# stm32_v0_8.net
KiCad netlist of a schematic drawn in EAGLE
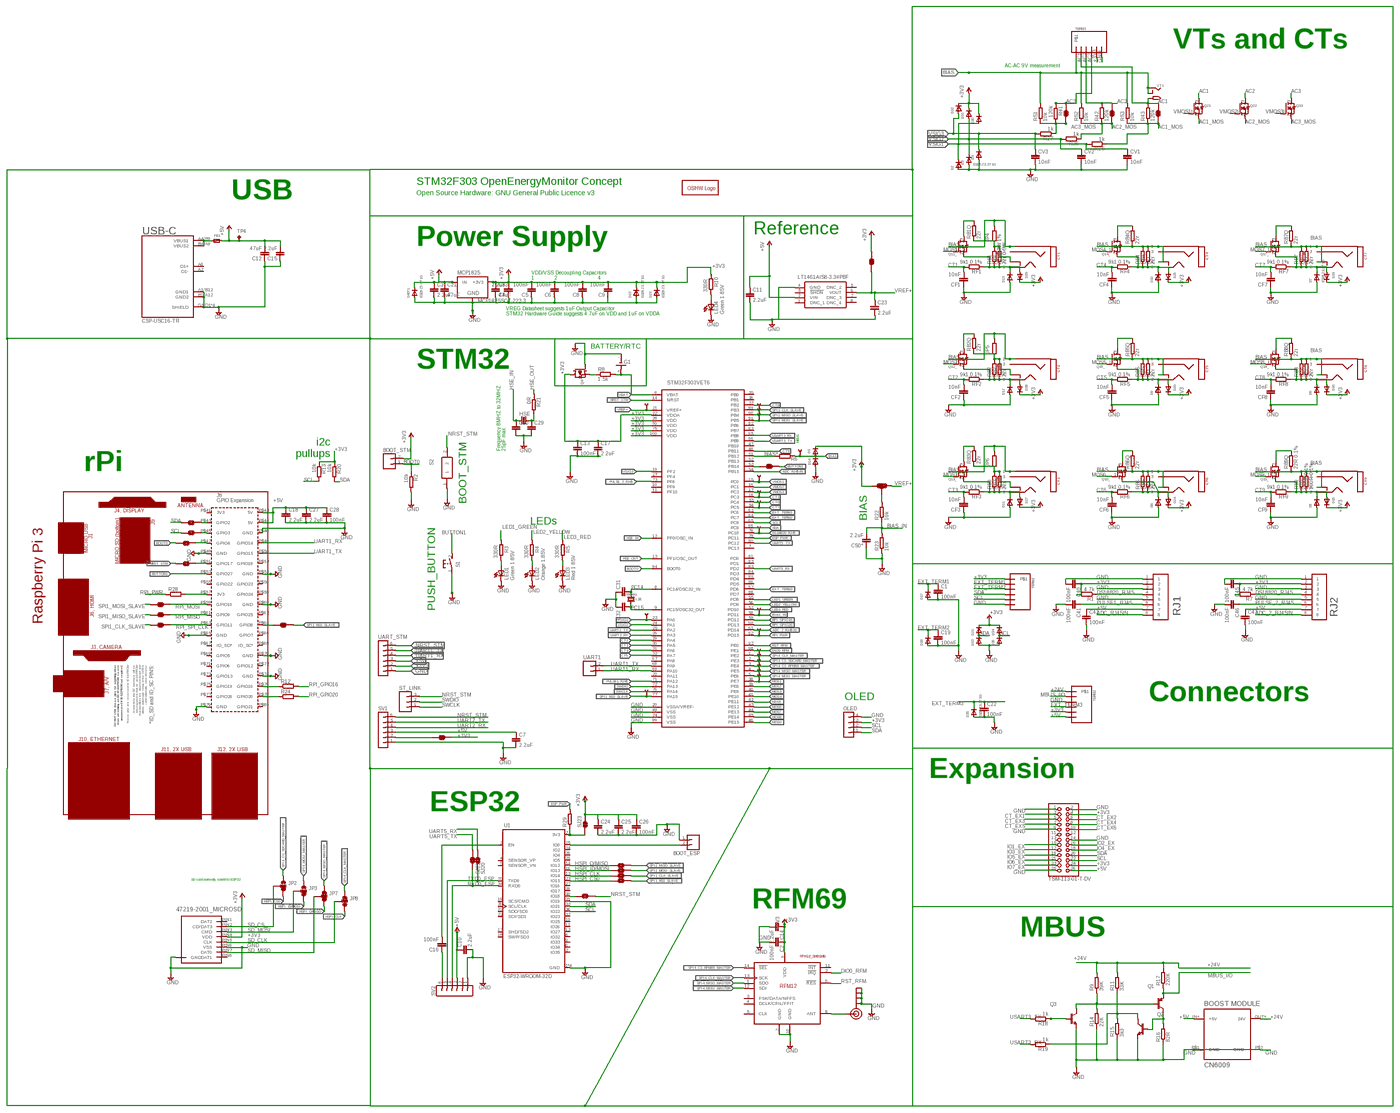
[diagram p0: schematic, sheet 1, overview]
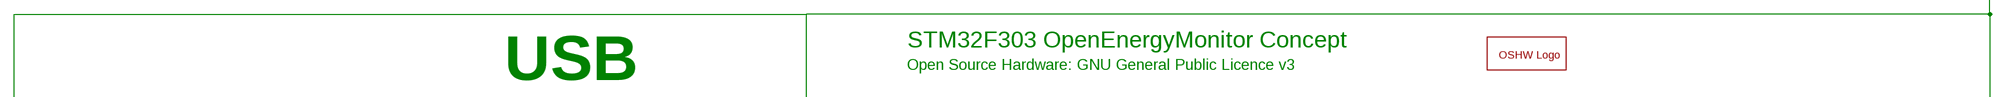
[diagram p1: schematic, sheet 1, part 1 of 4]
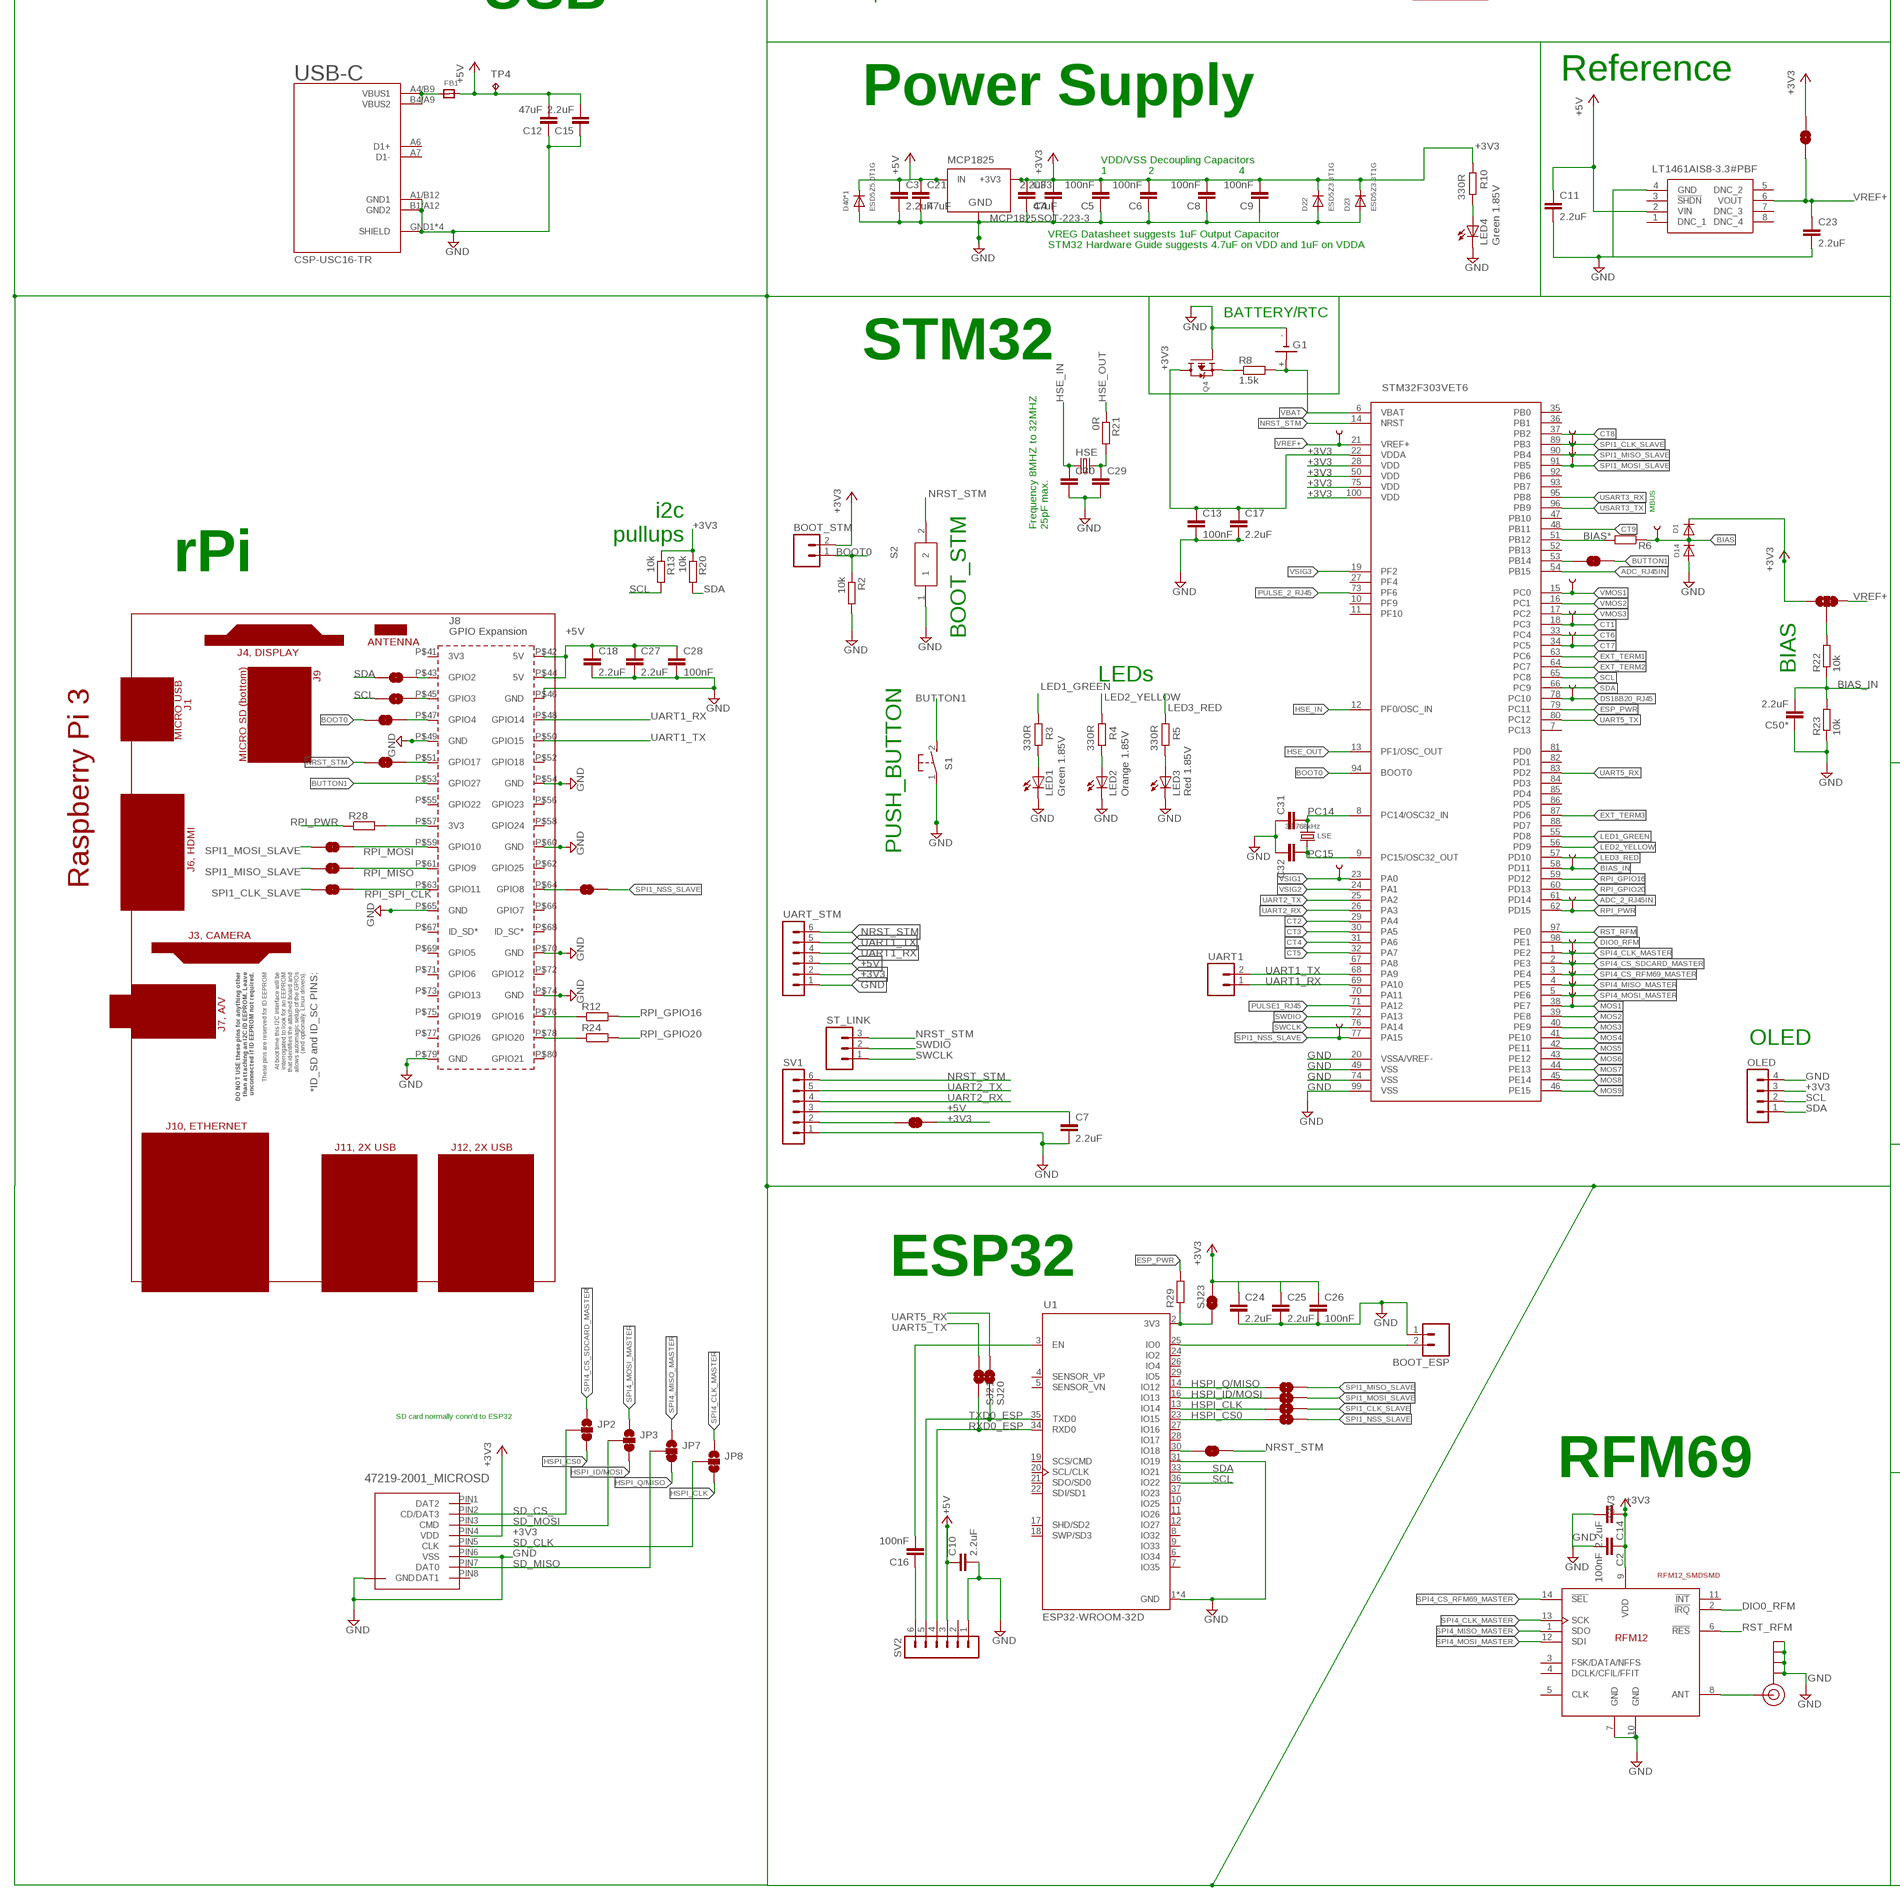
[diagram p2: schematic, sheet 1, part 2 of 4]
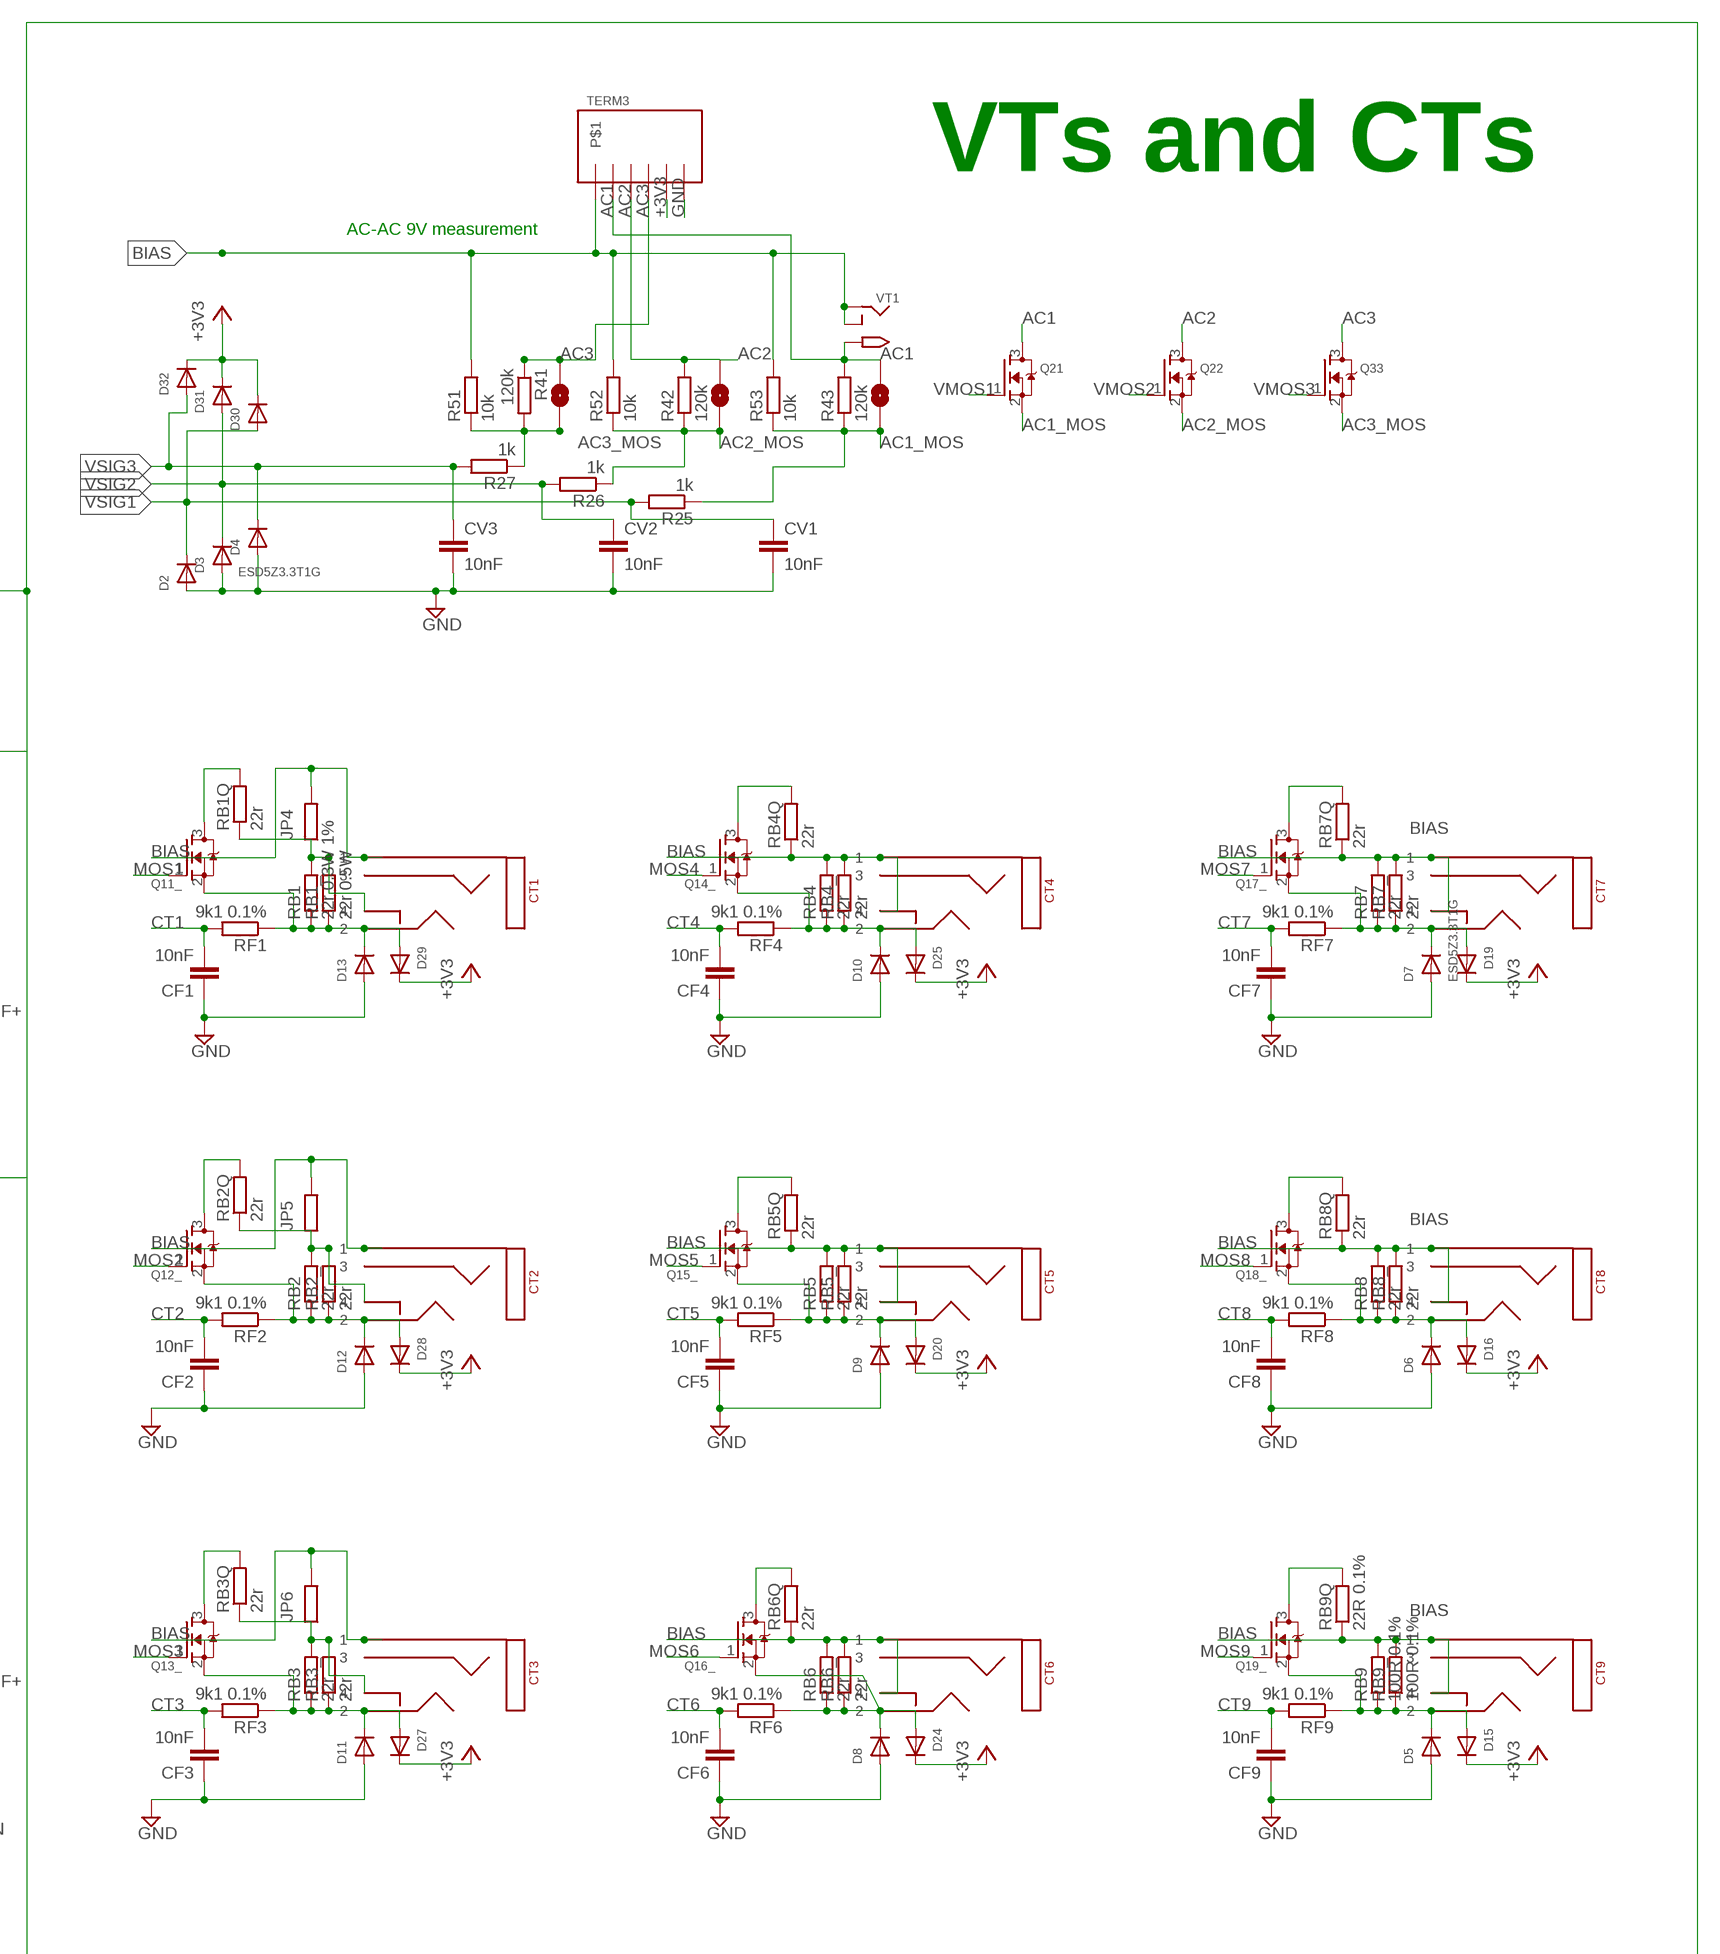
[diagram p3: schematic, sheet 1, part 3 of 4]
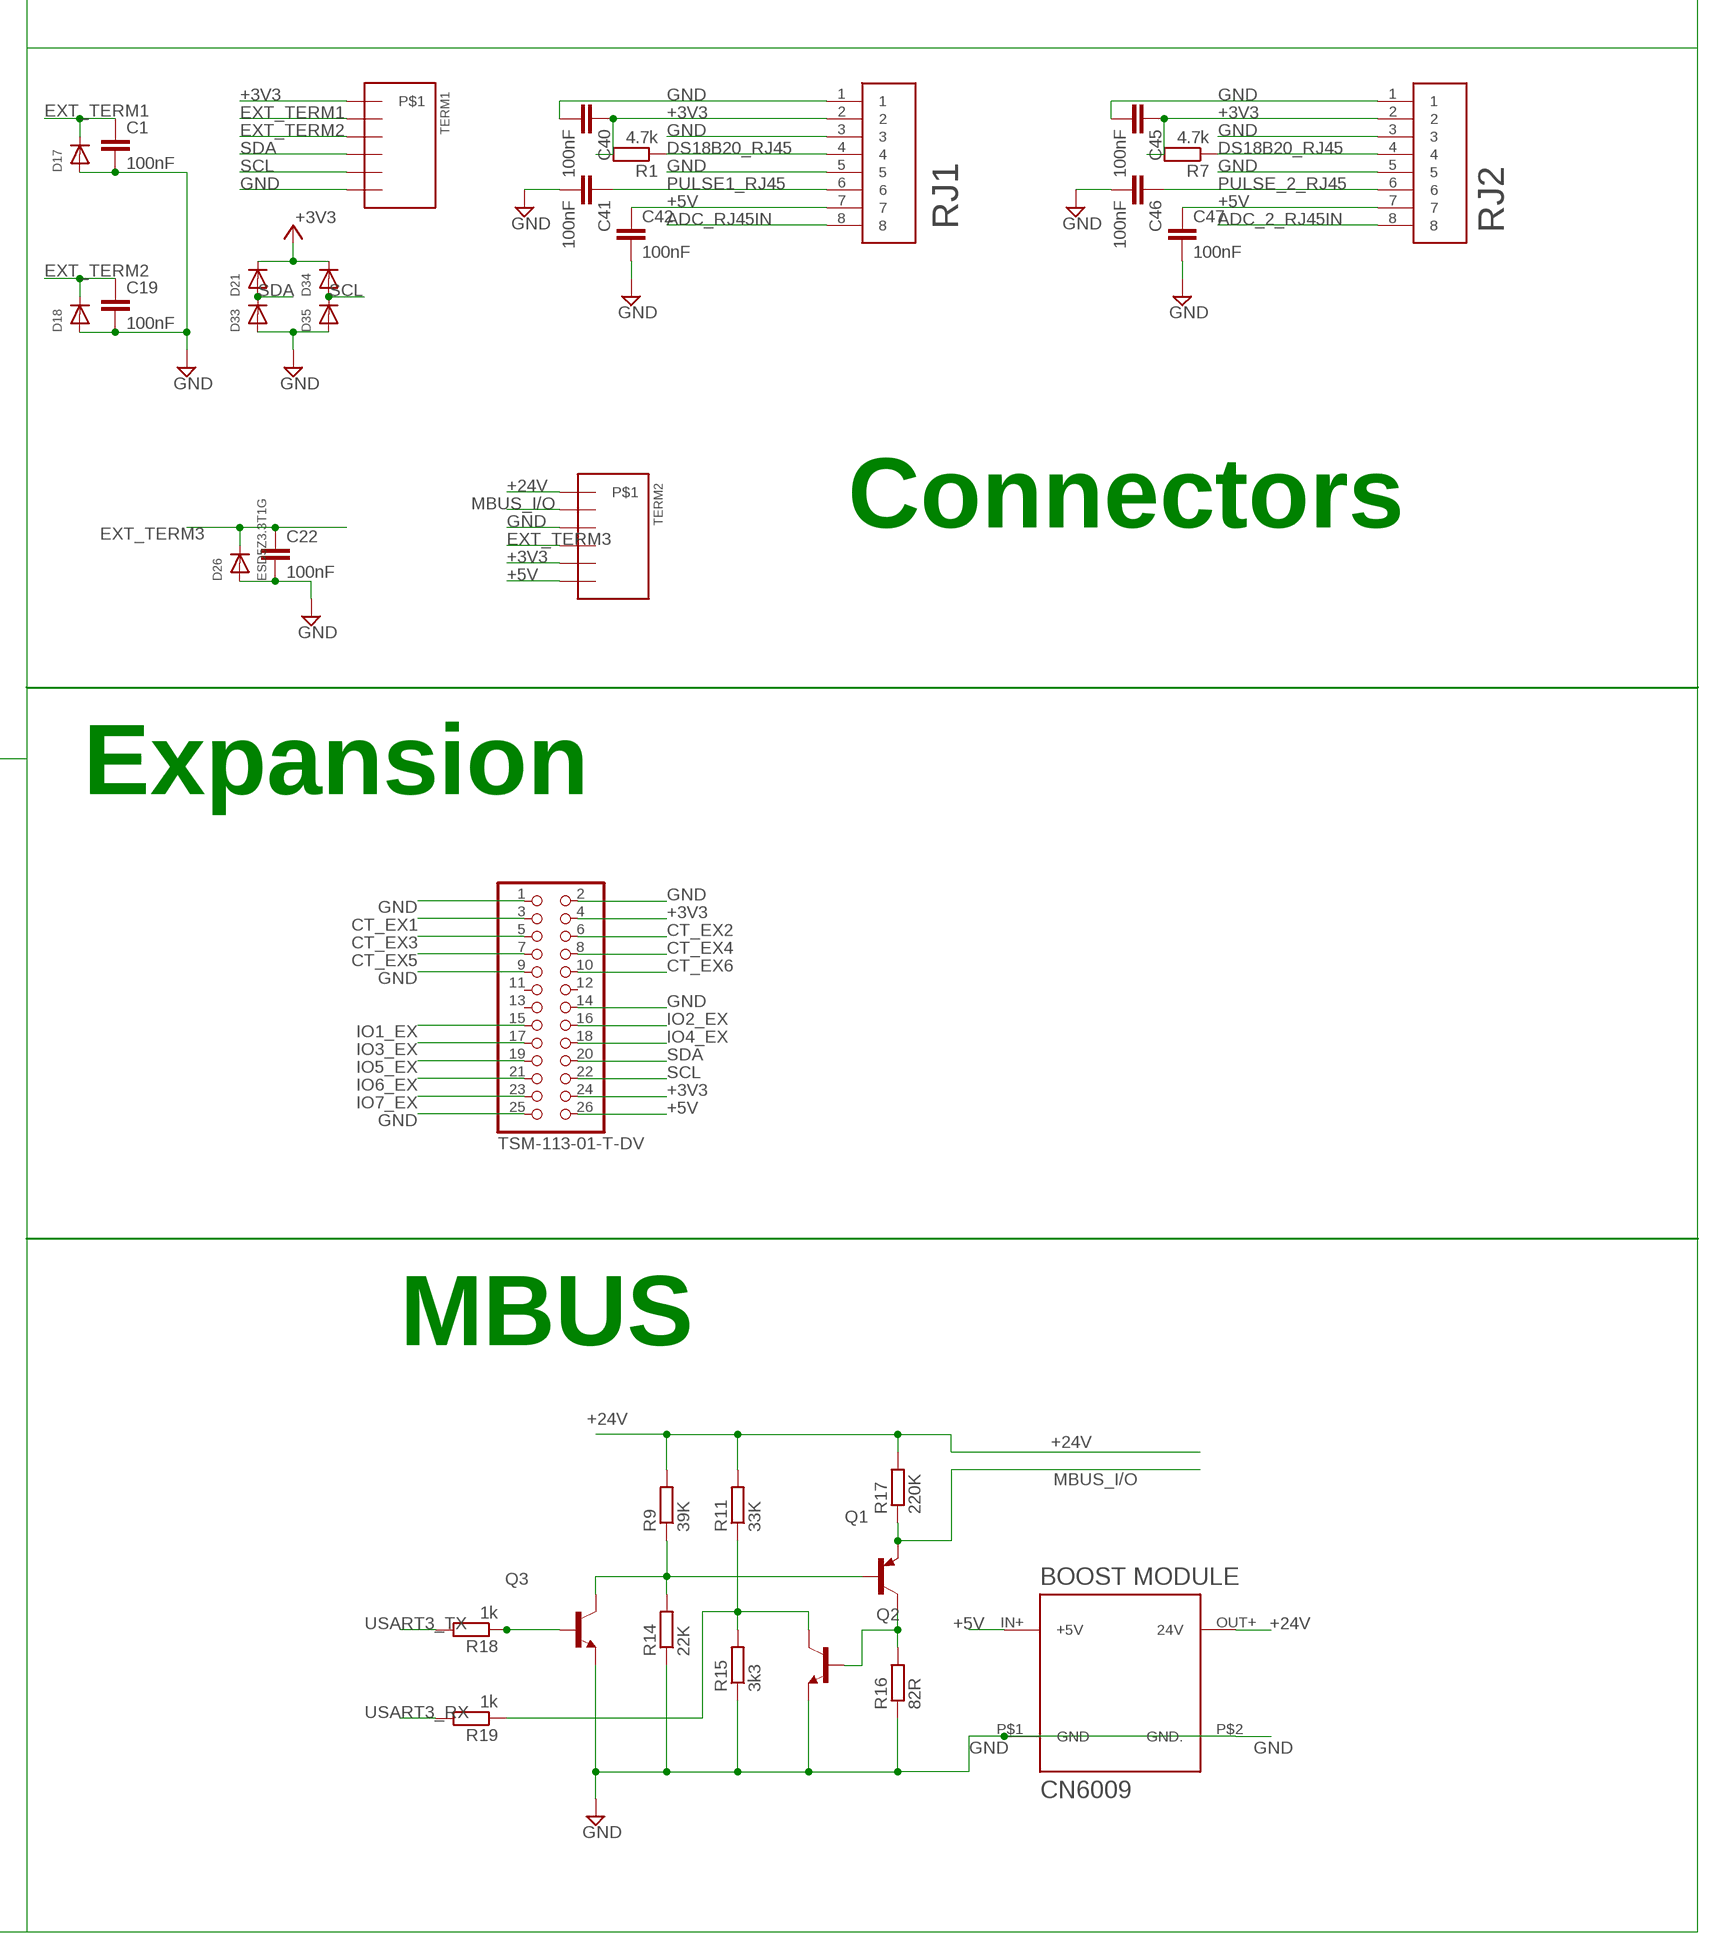
[diagram p4: schematic, sheet 1, part 4 of 4]

(export (version "E")
  (design (tool "Eeschema 10.0.6"))
  (components
    (comp (ref "BOOT_ESP")
      (value "M02PTH")
      (footprint "eagle-import:1X02")
      (libsource (lib "eagle-import") (part "M02PTH"))
    )
    (comp (ref "BOOT_STM")
      (value "M02PTH")
      (footprint "eagle-import:1X02")
      (libsource (lib "eagle-import") (part "M02PTH"))
    )
    (comp (ref "C1")
      (value "100nF")
      (footprint "eagle-import:C0603")
      (libsource (lib "eagle-import") (part "resistor_C-EUC0603"))
    )
    (comp (ref "C2")
      (value "100nF")
      (footprint "eagle-import:C0603")
      (libsource (lib "eagle-import") (part "resistor_C-EUC0603"))
    )
    (comp (ref "C3")
      (value "2.2uF")
      (footprint "eagle-import:C0805")
      (libsource (lib "eagle-import") (part "C-EUC0805"))
    )
    (comp (ref "C4")
      (value "2.2uF")
      (footprint "eagle-import:C0805")
      (libsource (lib "eagle-import") (part "C-EUC0805"))
    )
    (comp (ref "C5")
      (value "100nF")
      (footprint "eagle-import:C0603")
      (libsource (lib "eagle-import") (part "resistor_C-EUC0603"))
    )
    (comp (ref "C6")
      (value "100nF")
      (footprint "eagle-import:C0603")
      (libsource (lib "eagle-import") (part "resistor_C-EUC0603"))
    )
    (comp (ref "C7")
      (value "2.2uF")
      (footprint "eagle-import:C0805")
      (libsource (lib "eagle-import") (part "C-EUC0805"))
    )
    (comp (ref "C8")
      (value "100nF")
      (footprint "eagle-import:C0603")
      (libsource (lib "eagle-import") (part "resistor_C-EUC0603"))
    )
    (comp (ref "C9")
      (value "100nF")
      (footprint "eagle-import:C0603")
      (libsource (lib "eagle-import") (part "resistor_C-EUC0603"))
    )
    (comp (ref "C10")
      (value "2.2uF")
      (footprint "eagle-import:C0805")
      (libsource (lib "eagle-import") (part "C-EUC0805"))
    )
    (comp (ref "C11")
      (value "2.2uF")
      (footprint "eagle-import:C0805")
      (libsource (lib "eagle-import") (part "C-EUC0805"))
    )
    (comp (ref "C12")
      (value "47uF")
      (footprint "eagle-import:C0805")
      (libsource (lib "eagle-import") (part "C-EUC0805"))
    )
    (comp (ref "C13")
      (value "100nF")
      (footprint "eagle-import:C0603")
      (libsource (lib "eagle-import") (part "C-EUC0603"))
    )
    (comp (ref "C14")
      (value "2.2uF")
      (footprint "eagle-import:C0805")
      (libsource (lib "eagle-import") (part "C-EUC0805"))
    )
    (comp (ref "C15")
      (value "2.2uF")
      (footprint "eagle-import:C0805")
      (libsource (lib "eagle-import") (part "C-EUC0805"))
    )
    (comp (ref "C16")
      (value "100nF")
      (footprint "eagle-import:C0603")
      (libsource (lib "eagle-import") (part "resistor_C-EUC0603"))
    )
    (comp (ref "C17")
      (value "2.2uF")
      (footprint "eagle-import:C0805")
      (libsource (lib "eagle-import") (part "C-EUC0805"))
    )
    (comp (ref "C18")
      (value "2.2uF")
      (footprint "eagle-import:C0805")
      (libsource (lib "eagle-import") (part "C-EUC0805"))
    )
    (comp (ref "C19")
      (value "100nF")
      (footprint "eagle-import:C0603")
      (libsource (lib "eagle-import") (part "resistor_C-EUC0603"))
    )
    (comp (ref "C21")
      (value "47uF")
      (footprint "eagle-import:C0805")
      (libsource (lib "eagle-import") (part "C-EUC0805"))
    )
    (comp (ref "C22")
      (value "100nF")
      (footprint "eagle-import:C0603")
      (libsource (lib "eagle-import") (part "resistor_C-EUC0603"))
    )
    (comp (ref "C23")
      (value "2.2uF")
      (footprint "eagle-import:C0805")
      (libsource (lib "eagle-import") (part "C-EUC0805"))
    )
    (comp (ref "C24")
      (value "2.2uF")
      (footprint "eagle-import:C0805")
      (libsource (lib "eagle-import") (part "C-EUC0805"))
    )
    (comp (ref "C25")
      (value "2.2uF")
      (footprint "eagle-import:C0805")
      (libsource (lib "eagle-import") (part "C-EUC0805"))
    )
    (comp (ref "C26")
      (value "100nF")
      (footprint "eagle-import:C0603")
      (libsource (lib "eagle-import") (part "resistor_C-EUC0603"))
    )
    (comp (ref "C27")
      (value "2.2uF")
      (footprint "eagle-import:C0805")
      (libsource (lib "eagle-import") (part "C-EUC0805"))
    )
    (comp (ref "C28")
      (value "100nF")
      (footprint "eagle-import:C0603")
      (libsource (lib "eagle-import") (part "resistor_C-EUC0603"))
    )
    (comp (ref "C29")
      (value "15pF")
      (footprint "eagle-import:C0603")
      (libsource (lib "eagle-import") (part "C-EUC0603"))
    )
    (comp (ref "C30")
      (value "15pF")
      (footprint "eagle-import:C0603")
      (libsource (lib "eagle-import") (part "C-EUC0603"))
    )
    (comp (ref "C31")
      (value "10pF")
      (footprint "eagle-import:C0603")
      (libsource (lib "eagle-import") (part "C-EUC0603"))
    )
    (comp (ref "C32")
      (value "10pF")
      (footprint "eagle-import:C0603")
      (libsource (lib "eagle-import") (part "C-EUC0603"))
    )
    (comp (ref "C33")
      (value "47uF")
      (footprint "eagle-import:C0805")
      (libsource (lib "eagle-import") (part "C-EUC0805"))
    )
    (comp (ref "C40")
      (value "100nF")
      (footprint "eagle-import:C0603")
      (libsource (lib "eagle-import") (part "resistor_C-EUC0603"))
    )
    (comp (ref "C41")
      (value "100nF")
      (footprint "eagle-import:C0603")
      (libsource (lib "eagle-import") (part "resistor_C-EUC0603"))
    )
    (comp (ref "C42")
      (value "100nF")
      (footprint "eagle-import:C0603")
      (libsource (lib "eagle-import") (part "resistor_C-EUC0603"))
    )
    (comp (ref "C45")
      (value "100nF")
      (footprint "eagle-import:C0603")
      (libsource (lib "eagle-import") (part "resistor_C-EUC0603"))
    )
    (comp (ref "C46")
      (value "100nF")
      (footprint "eagle-import:C0603")
      (libsource (lib "eagle-import") (part "resistor_C-EUC0603"))
    )
    (comp (ref "C47")
      (value "100nF")
      (footprint "eagle-import:C0603")
      (libsource (lib "eagle-import") (part "resistor_C-EUC0603"))
    )
    (comp (ref "C50*")
      (value "2.2uF")
      (footprint "eagle-import:C0805")
      (libsource (lib "eagle-import") (part "C-EUC0805"))
    )
    (comp (ref "CF1")
      (value "10nF")
      (footprint "eagle-import:C0603")
      (libsource (lib "eagle-import") (part "resistor_C-EUC0603"))
    )
    (comp (ref "CF2")
      (value "10nF")
      (footprint "eagle-import:C0603")
      (libsource (lib "eagle-import") (part "resistor_C-EUC0603"))
    )
    (comp (ref "CF3")
      (value "10nF")
      (footprint "eagle-import:C0603")
      (libsource (lib "eagle-import") (part "resistor_C-EUC0603"))
    )
    (comp (ref "CF4")
      (value "10nF")
      (footprint "eagle-import:C0603")
      (libsource (lib "eagle-import") (part "resistor_C-EUC0603"))
    )
    (comp (ref "CF5")
      (value "10nF")
      (footprint "eagle-import:C0603")
      (libsource (lib "eagle-import") (part "resistor_C-EUC0603"))
    )
    (comp (ref "CF6")
      (value "10nF")
      (footprint "eagle-import:C0603")
      (libsource (lib "eagle-import") (part "resistor_C-EUC0603"))
    )
    (comp (ref "CF7")
      (value "10nF")
      (footprint "eagle-import:C0603")
      (libsource (lib "eagle-import") (part "resistor_C-EUC0603"))
    )
    (comp (ref "CF8")
      (value "10nF")
      (footprint "eagle-import:C0603")
      (libsource (lib "eagle-import") (part "resistor_C-EUC0603"))
    )
    (comp (ref "CF9")
      (value "10nF")
      (footprint "eagle-import:C0603")
      (libsource (lib "eagle-import") (part "resistor_C-EUC0603"))
    )
    (comp (ref "CT1")
      (value "SJ-3523-SMT")
      (footprint "eagle-import:STEREO_SMT")
      (libsource (lib "eagle-import") (part "STEREO_SMD"))
    )
    (comp (ref "CT2")
      (value "SJ-3523-SMT")
      (footprint "eagle-import:STEREO_SMT")
      (libsource (lib "eagle-import") (part "STEREO_SMD"))
    )
    (comp (ref "CT3")
      (value "SJ-3523-SMT")
      (footprint "eagle-import:STEREO_SMT")
      (libsource (lib "eagle-import") (part "STEREO_SMD"))
    )
    (comp (ref "CT4")
      (value "SJ-3523-SMT")
      (footprint "eagle-import:STEREO_SMT")
      (libsource (lib "eagle-import") (part "STEREO_SMD"))
    )
    (comp (ref "CT5")
      (value "SJ-3523-SMT")
      (footprint "eagle-import:STEREO_SMT")
      (libsource (lib "eagle-import") (part "STEREO_SMD"))
    )
    (comp (ref "CT6")
      (value "SJ-3523-SMT")
      (footprint "eagle-import:STEREO_SMT")
      (libsource (lib "eagle-import") (part "STEREO_SMD"))
    )
    (comp (ref "CT7")
      (value "SJ-3523-SMT")
      (footprint "eagle-import:STEREO_SMT")
      (libsource (lib "eagle-import") (part "STEREO_SMD"))
    )
    (comp (ref "CT8")
      (value "SJ-3523-SMT")
      (footprint "eagle-import:STEREO_SMT")
      (libsource (lib "eagle-import") (part "STEREO_SMD"))
    )
    (comp (ref "CT9")
      (value "SJ-3523-SMT")
      (footprint "eagle-import:STEREO_SMT")
      (libsource (lib "eagle-import") (part "STEREO_SMD"))
    )
    (comp (ref "CV1")
      (value "10nF")
      (footprint "eagle-import:C0603")
      (libsource (lib "eagle-import") (part "resistor_C-EUC0603"))
    )
    (comp (ref "CV2")
      (value "10nF")
      (footprint "eagle-import:C0603")
      (libsource (lib "eagle-import") (part "resistor_C-EUC0603"))
    )
    (comp (ref "CV3")
      (value "10nF")
      (footprint "eagle-import:C0603")
      (libsource (lib "eagle-import") (part "resistor_C-EUC0603"))
    )
    (comp (ref "D1")
      (value "ESD5Z3.3T1G")
      (footprint "eagle-import:SOD-523")
      (libsource (lib "eagle-import") (part "DIODESOD-523"))
    )
    (comp (ref "D2")
      (value "ESD5Z3.3T1G")
      (footprint "eagle-import:SOD-523")
      (libsource (lib "eagle-import") (part "DIODESOD-523"))
    )
    (comp (ref "D3")
      (value "ESD5Z3.3T1G")
      (footprint "eagle-import:SOD-523")
      (libsource (lib "eagle-import") (part "DIODESOD-523"))
    )
    (comp (ref "D4")
      (value "ESD5Z3.3T1G")
      (footprint "eagle-import:SOD-523")
      (libsource (lib "eagle-import") (part "DIODESOD-523"))
    )
    (comp (ref "D5")
      (value "ESD5Z3.3T1G")
      (footprint "eagle-import:SOD-523")
      (libsource (lib "eagle-import") (part "DIODESOD-523"))
    )
    (comp (ref "D6")
      (value "ESD5Z3.3T1G")
      (footprint "eagle-import:SOD-523")
      (libsource (lib "eagle-import") (part "DIODESOD-523"))
    )
    (comp (ref "D7")
      (value "ESD5Z3.3T1G")
      (footprint "eagle-import:SOD-523")
      (libsource (lib "eagle-import") (part "DIODESOD-523"))
    )
    (comp (ref "D8")
      (value "ESD5Z3.3T1G")
      (footprint "eagle-import:SOD-523")
      (libsource (lib "eagle-import") (part "DIODESOD-523"))
    )
    (comp (ref "D9")
      (value "ESD5Z3.3T1G")
      (footprint "eagle-import:SOD-523")
      (libsource (lib "eagle-import") (part "DIODESOD-523"))
    )
    (comp (ref "D10")
      (value "ESD5Z3.3T1G")
      (footprint "eagle-import:SOD-523")
      (libsource (lib "eagle-import") (part "DIODESOD-523"))
    )
    (comp (ref "D11")
      (value "ESD5Z3.3T1G")
      (footprint "eagle-import:SOD-523")
      (libsource (lib "eagle-import") (part "DIODESOD-523"))
    )
    (comp (ref "D12")
      (value "ESD5Z3.3T1G")
      (footprint "eagle-import:SOD-523")
      (libsource (lib "eagle-import") (part "DIODESOD-523"))
    )
    (comp (ref "D13")
      (value "ESD5Z3.3T1G")
      (footprint "eagle-import:SOD-523")
      (libsource (lib "eagle-import") (part "DIODESOD-523"))
    )
    (comp (ref "D14")
      (value "ESD5Z3.3T1G")
      (footprint "eagle-import:SOD-523")
      (libsource (lib "eagle-import") (part "DIODESOD-523"))
    )
    (comp (ref "D15")
      (value "ESD5Z3.3T1G")
      (footprint "eagle-import:SOD-523")
      (libsource (lib "eagle-import") (part "DIODESOD-523"))
    )
    (comp (ref "D16")
      (value "ESD5Z3.3T1G")
      (footprint "eagle-import:SOD-523")
      (libsource (lib "eagle-import") (part "DIODESOD-523"))
    )
    (comp (ref "D17")
      (value "ESD5Z3.3T1G")
      (footprint "eagle-import:SOD-523")
      (libsource (lib "eagle-import") (part "DIODESOD-523"))
    )
    (comp (ref "D18")
      (value "ESD5Z3.3T1G")
      (footprint "eagle-import:SOD-523")
      (libsource (lib "eagle-import") (part "DIODESOD-523"))
    )
    (comp (ref "D19")
      (value "ESD5Z3.3T1G")
      (footprint "eagle-import:SOD-523")
      (libsource (lib "eagle-import") (part "DIODESOD-523"))
    )
    (comp (ref "D20")
      (value "ESD5Z3.3T1G")
      (footprint "eagle-import:SOD-523")
      (libsource (lib "eagle-import") (part "DIODESOD-523"))
    )
    (comp (ref "D21")
      (value "ESD5Z3.3T1G")
      (footprint "eagle-import:SOD-523")
      (libsource (lib "eagle-import") (part "DIODESOD-523"))
    )
    (comp (ref "D22")
      (value "ESD5Z3.3T1G")
      (footprint "eagle-import:SOD-523")
      (libsource (lib "eagle-import") (part "DIODESOD-523"))
    )
    (comp (ref "D23")
      (value "ESD5Z3.3T1G")
      (footprint "eagle-import:SOD-523")
      (libsource (lib "eagle-import") (part "DIODESOD-523"))
    )
    (comp (ref "D24")
      (value "ESD5Z3.3T1G")
      (footprint "eagle-import:SOD-523")
      (libsource (lib "eagle-import") (part "DIODESOD-523"))
    )
    (comp (ref "D25")
      (value "ESD5Z3.3T1G")
      (footprint "eagle-import:SOD-523")
      (libsource (lib "eagle-import") (part "DIODESOD-523"))
    )
    (comp (ref "D26")
      (value "ESD5Z3.3T1G")
      (footprint "eagle-import:SOD-523")
      (libsource (lib "eagle-import") (part "DIODESOD-523"))
    )
    (comp (ref "D27")
      (value "ESD5Z3.3T1G")
      (footprint "eagle-import:SOD-523")
      (libsource (lib "eagle-import") (part "DIODESOD-523"))
    )
    (comp (ref "D28")
      (value "ESD5Z3.3T1G")
      (footprint "eagle-import:SOD-523")
      (libsource (lib "eagle-import") (part "DIODESOD-523"))
    )
    (comp (ref "D29")
      (value "ESD5Z3.3T1G")
      (footprint "eagle-import:SOD-523")
      (libsource (lib "eagle-import") (part "DIODESOD-523"))
    )
    (comp (ref "D30")
      (value "ESD5Z3.3T1G")
      (footprint "eagle-import:SOD-523")
      (libsource (lib "eagle-import") (part "DIODESOD-523"))
    )
    (comp (ref "D31")
      (value "ESD5Z3.3T1G")
      (footprint "eagle-import:SOD-523")
      (libsource (lib "eagle-import") (part "DIODESOD-523"))
    )
    (comp (ref "D32")
      (value "ESD5Z3.3T1G")
      (footprint "eagle-import:SOD-523")
      (libsource (lib "eagle-import") (part "DIODESOD-523"))
    )
    (comp (ref "D33")
      (value "ESD5Z3.3T1G")
      (footprint "eagle-import:SOD-523")
      (libsource (lib "eagle-import") (part "DIODESOD-523"))
    )
    (comp (ref "D34")
      (value "ESD5Z3.3T1G")
      (footprint "eagle-import:SOD-523")
      (libsource (lib "eagle-import") (part "DIODESOD-523"))
    )
    (comp (ref "D35")
      (value "ESD5Z3.3T1G")
      (footprint "eagle-import:SOD-523")
      (libsource (lib "eagle-import") (part "DIODESOD-523"))
    )
    (comp (ref "D40*1")
      (value "ESD5Z5.0T1G")
      (footprint "eagle-import:SOD-523")
      (libsource (lib "eagle-import") (part "DIODESOD-523"))
    )
    (comp (ref "EXPANSION")
      (value "TSM-113-01-T-DV")
      (footprint "eagle-import:2X13_SMT")
      (libsource (lib "eagle-import") (part "PINHD-2X13SMT"))
    )
    (comp (ref "FB1")
      (value "FERRITE")
      (footprint "eagle-import:0603")
      (libsource (lib "eagle-import") (part "FERRITE"))
    )
    (comp (ref "G1")
      (value "CH291-1220LF")
      (footprint "eagle-import:CH291-1220LF")
      (fields (field (name "MF") "Multicomp"))
      (libsource (lib "eagle-import") (part "CH291-1220LF"))
    )
    (comp (ref "GOLD_ORB_SM1")
      (value "OSHWLOGOLOGO8MM")
      (footprint "eagle-import:OSHW_8MM")
      (libsource (lib "eagle-import") (part "OSHWLOGOLOGO8MM"))
    )
    (comp (ref "HSE")
      (value "406C35E08M00000")
      (footprint "eagle-import:CTS406")
      (libsource (lib "eagle-import") (part "CRYSTALCTS406"))
    )
    (comp (ref "J$1")
      (value "SMA_EDGE")
      (footprint "eagle-import:SMA-EDGE")
      (libsource (lib "eagle-import") (part "SMA_EDGE"))
    )
    (comp (ref "J1")
      (value "SOLDERJUMPERNO")
      (footprint "eagle-import:SJ_2S-NO")
      (libsource (lib "eagle-import") (part "SOLDERJUMPERNO"))
    )
    (comp (ref "JP1")
      (value "JUMPER-SMT_3_1-NC_TRACE_NO-SILK")
      (footprint "eagle-import:SMT-JUMPER_3_1-NC_TRACE_NO-SILK")
      (libsource (lib "eagle-import") (part "JUMPER-SMT_3_1-NC_TRACE_NO-SILK"))
    )
    (comp (ref "JP2")
      (value "JUMPER-SMT_3_1-NC_TRACE_SILK")
      (footprint "eagle-import:SMT-JUMPER_3_1-NC_TRACE_SILK")
      (libsource (lib "eagle-import") (part "JUMPER-SMT_3_1-NC_TRACE_SILK"))
    )
    (comp (ref "JP3")
      (value "JUMPER-SMT_3_1-NC_TRACE_SILK")
      (footprint "eagle-import:SMT-JUMPER_3_1-NC_TRACE_SILK")
      (libsource (lib "eagle-import") (part "JUMPER-SMT_3_1-NC_TRACE_SILK"))
    )
    (comp (ref "JP4")
      (value "R-EU_R0603")
      (footprint "eagle-import:R0603")
      (libsource (lib "eagle-import") (part "R-EU_R0603"))
    )
    (comp (ref "JP5")
      (value "R-EU_R0603")
      (footprint "eagle-import:R0603")
      (libsource (lib "eagle-import") (part "R-EU_R0603"))
    )
    (comp (ref "JP6")
      (value "R-EU_R0603")
      (footprint "eagle-import:R0603")
      (libsource (lib "eagle-import") (part "R-EU_R0603"))
    )
    (comp (ref "JP7")
      (value "JUMPER-SMT_3_1-NC_TRACE_SILK")
      (footprint "eagle-import:SMT-JUMPER_3_1-NC_TRACE_SILK")
      (libsource (lib "eagle-import") (part "JUMPER-SMT_3_1-NC_TRACE_SILK"))
    )
    (comp (ref "JP8")
      (value "JUMPER-SMT_3_1-NC_TRACE_SILK")
      (footprint "eagle-import:SMT-JUMPER_3_1-NC_TRACE_SILK")
      (libsource (lib "eagle-import") (part "JUMPER-SMT_3_1-NC_TRACE_SILK"))
    )
    (comp (ref "LED1")
      (value "Green 1.85V")
      (footprint "eagle-import:CHIP-LED0805")
      (libsource (lib "eagle-import") (part "LEDCHIP-LED0805"))
    )
    (comp (ref "LED2")
      (value "Orange 1.85V")
      (footprint "eagle-import:CHIP-LED0805")
      (libsource (lib "eagle-import") (part "LEDCHIP-LED0805"))
    )
    (comp (ref "LED3")
      (value "Red 1.85V")
      (footprint "eagle-import:CHIP-LED0805")
      (libsource (lib "eagle-import") (part "LEDCHIP-LED0805"))
    )
    (comp (ref "LED4")
      (value "Green 1.85V")
      (footprint "eagle-import:CHIP-LED0805")
      (libsource (lib "eagle-import") (part "LEDCHIP-LED0805"))
    )
    (comp (ref "LSE")
      (value "32.768kHz")
      (footprint "eagle-import:CRYSTAL_8X3.8")
      (libsource (lib "eagle-import") (part "CRYSTAL8X3.8SMT"))
    )
    (comp (ref "MCP1825")
      (value "MCP1825SOT-223-3")
      (footprint "eagle-import:SOT-223")
      (fields (field (name "MPN") "MCP1825S-3302E/DB"))
      (libsource (lib "eagle-import") (part "MCP1825SOT-223-3"))
    )
    (comp (ref "OLED")
      (value "MA04-1-OLEDOLED")
      (footprint "eagle-import:MA04-1-OLED")
      (libsource (lib "eagle-import") (part "MA04-1-OLEDOLED"))
    )
    (comp (ref "PCB2")
      (value "RPI3YA")
      (footprint "eagle-import:RPI3MIRROR2")
      (fields (field (name "MPN") "M20-7872042"))
      (libsource (lib "eagle-import") (part "RPI3YA"))
    )
    (comp (ref "PS1")
      (value "LT1461AIS8-3.3#PBF")
      (footprint "eagle-import:SOIC127P599X175-8N")
      (fields (field (name "RS_PART_NUMBER") "7618279P"))
      (libsource (lib "eagle-import") (part "LT1461AIS8-3.3#PBF"))
    )
    (comp (ref "Q1")
      (value "MMBT3906")
      (footprint "eagle-import:SOT23")
      (fields
        (field (name "DIGIKEY_PART_NUMBER") "MMBT3906FSCT-ND")
        (field (name "MANUFACTURER") "ON Semiconductor")
        (field (name "CREATED_BY") "PCB Layout")
      )
      (libsource (lib "eagle-import") (part "MMBT3906"))
    )
    (comp (ref "Q2")
      (value "MMBT3904")
      (footprint "eagle-import:SOT23")
      (fields
        (field (name "DIGIKEY_PART_NUMBER") "MMBT3904FSCT-ND")
        (field (name "MANUFACTURER") "ON Semiconductor")
        (field (name "CREATED_BY") "PCB Layout")
      )
      (libsource (lib "eagle-import") (part "MMBT3904"))
    )
    (comp (ref "Q3")
      (value "MMBT3904")
      (footprint "eagle-import:SOT23")
      (fields
        (field (name "DIGIKEY_PART_NUMBER") "MMBT3904FSCT-ND")
        (field (name "MANUFACTURER") "ON Semiconductor")
        (field (name "CREATED_BY") "PCB Layout")
      )
      (libsource (lib "eagle-import") (part "MMBT3904"))
    )
    (comp (ref "Q4")
      (value "MOSFET-P")
      (footprint "eagle-import:SOT23-R")
      (libsource (lib "eagle-import") (part "MOSFET-P"))
    )
    (comp (ref "Q11_")
      (value "MOSFET-NREFLOW")
      (footprint "eagle-import:SOT23")
      (fields (field (name "MPN") "FDV303N"))
      (libsource (lib "eagle-import") (part "MOSFET-NREFLOW"))
    )
    (comp (ref "Q12_")
      (value "MOSFET-NREFLOW")
      (footprint "eagle-import:SOT23")
      (fields (field (name "MPN") "FDV303N"))
      (libsource (lib "eagle-import") (part "MOSFET-NREFLOW"))
    )
    (comp (ref "Q13_")
      (value "MOSFET-NREFLOW")
      (footprint "eagle-import:SOT23")
      (fields (field (name "MPN") "FDV303N"))
      (libsource (lib "eagle-import") (part "MOSFET-NREFLOW"))
    )
    (comp (ref "Q14_")
      (value "MOSFET-NREFLOW")
      (footprint "eagle-import:SOT23")
      (fields (field (name "MPN") "FDV303N"))
      (libsource (lib "eagle-import") (part "MOSFET-NREFLOW"))
    )
    (comp (ref "Q15_")
      (value "MOSFET-NREFLOW")
      (footprint "eagle-import:SOT23")
      (fields (field (name "MPN") "FDV303N"))
      (libsource (lib "eagle-import") (part "MOSFET-NREFLOW"))
    )
    (comp (ref "Q16_")
      (value "MOSFET-NREFLOW")
      (footprint "eagle-import:SOT23")
      (fields (field (name "MPN") "FDV303N"))
      (libsource (lib "eagle-import") (part "MOSFET-NREFLOW"))
    )
    (comp (ref "Q17_")
      (value "MOSFET-NREFLOW")
      (footprint "eagle-import:SOT23")
      (fields (field (name "MPN") "FDV303N"))
      (libsource (lib "eagle-import") (part "MOSFET-NREFLOW"))
    )
    (comp (ref "Q18_")
      (value "MOSFET-NREFLOW")
      (footprint "eagle-import:SOT23")
      (fields (field (name "MPN") "FDV303N"))
      (libsource (lib "eagle-import") (part "MOSFET-NREFLOW"))
    )
    (comp (ref "Q19_")
      (value "MOSFET-NREFLOW")
      (footprint "eagle-import:SOT23")
      (fields (field (name "MPN") "FDV303N"))
      (libsource (lib "eagle-import") (part "MOSFET-NREFLOW"))
    )
    (comp (ref "Q21")
      (value "MOSFET-NREFLOW")
      (footprint "eagle-import:SOT23")
      (fields (field (name "MPN") "FDV303N"))
      (libsource (lib "eagle-import") (part "MOSFET-NREFLOW"))
    )
    (comp (ref "Q22")
      (value "MOSFET-NREFLOW")
      (footprint "eagle-import:SOT23")
      (fields (field (name "MPN") "FDV303N"))
      (libsource (lib "eagle-import") (part "MOSFET-NREFLOW"))
    )
    (comp (ref "Q33")
      (value "MOSFET-NREFLOW")
      (footprint "eagle-import:SOT23")
      (fields (field (name "MPN") "FDV303N"))
      (libsource (lib "eagle-import") (part "MOSFET-NREFLOW"))
    )
    (comp (ref "R1")
      (value "4.7k")
      (footprint "eagle-import:R0603")
      (libsource (lib "eagle-import") (part "resistor_R-EU_R0603"))
    )
    (comp (ref "R2")
      (value "10k")
      (footprint "eagle-import:R0603")
      (libsource (lib "eagle-import") (part "resistor_R-EU_R0603"))
    )
    (comp (ref "R3")
      (value "330R")
      (footprint "eagle-import:R0603")
      (libsource (lib "eagle-import") (part "R-EU_R0603"))
    )
    (comp (ref "R4")
      (value "330R")
      (footprint "eagle-import:R0603")
      (libsource (lib "eagle-import") (part "R-EU_R0603"))
    )
    (comp (ref "R5")
      (value "330R")
      (footprint "eagle-import:R0603")
      (libsource (lib "eagle-import") (part "R-EU_R0603"))
    )
    (comp (ref "R6")
      (value "0R")
      (footprint "eagle-import:R0603")
      (libsource (lib "eagle-import") (part "resistor_R-EU_R0603"))
    )
    (comp (ref "R7")
      (value "4.7k")
      (footprint "eagle-import:R0603")
      (libsource (lib "eagle-import") (part "resistor_R-EU_R0603"))
    )
    (comp (ref "R8")
      (value "1.5k")
      (footprint "eagle-import:R0603")
      (libsource (lib "eagle-import") (part "resistor_R-EU_R0603"))
    )
    (comp (ref "R9")
      (value "39K")
      (footprint "eagle-import:R0603")
      (libsource (lib "eagle-import") (part "R-EU_R0603"))
    )
    (comp (ref "R10")
      (value "330R")
      (footprint "eagle-import:R0603")
      (libsource (lib "eagle-import") (part "R-EU_R0603"))
    )
    (comp (ref "R11")
      (value "33K")
      (footprint "eagle-import:R0603")
      (libsource (lib "eagle-import") (part "R-EU_R0603"))
    )
    (comp (ref "R12")
      (value "10K")
      (footprint "eagle-import:R0603")
      (libsource (lib "eagle-import") (part "R-EU_R0603"))
    )
    (comp (ref "R13")
      (value "10k")
      (footprint "eagle-import:R0603")
      (libsource (lib "eagle-import") (part "resistor_R-EU_R0603"))
    )
    (comp (ref "R14")
      (value "22K")
      (footprint "eagle-import:R0603")
      (libsource (lib "eagle-import") (part "R-EU_R0603"))
    )
    (comp (ref "R15")
      (value "3k3")
      (footprint "eagle-import:R0603")
      (libsource (lib "eagle-import") (part "R-EU_R0603"))
    )
    (comp (ref "R16")
      (value "82R")
      (footprint "eagle-import:R0603")
      (libsource (lib "eagle-import") (part "R-EU_R0603"))
    )
    (comp (ref "R17")
      (value "220K")
      (footprint "eagle-import:R0603")
      (libsource (lib "eagle-import") (part "R-EU_R0603"))
    )
    (comp (ref "R18")
      (value "1k")
      (footprint "eagle-import:R0603")
      (libsource (lib "eagle-import") (part "R-EU_R0603"))
    )
    (comp (ref "R19")
      (value "1k")
      (footprint "eagle-import:R0603")
      (libsource (lib "eagle-import") (part "R-EU_R0603"))
    )
    (comp (ref "R20")
      (value "10k")
      (footprint "eagle-import:R0603")
      (libsource (lib "eagle-import") (part "resistor_R-EU_R0603"))
    )
    (comp (ref "R21")
      (value "0R")
      (footprint "eagle-import:R0603")
      (libsource (lib "eagle-import") (part "resistor_R-EU_R0603"))
    )
    (comp (ref "R22")
      (value "10k")
      (footprint "eagle-import:R0603")
      (libsource (lib "eagle-import") (part "resistor_R-EU_R0603"))
    )
    (comp (ref "R23")
      (value "10k")
      (footprint "eagle-import:R0603")
      (libsource (lib "eagle-import") (part "resistor_R-EU_R0603"))
    )
    (comp (ref "R24")
      (value "10K")
      (footprint "eagle-import:R0603")
      (libsource (lib "eagle-import") (part "R-EU_R0603"))
    )
    (comp (ref "R25")
      (value "1k")
      (footprint "eagle-import:R0603")
      (libsource (lib "eagle-import") (part "resistor_R-EU_R0603"))
    )
    (comp (ref "R26")
      (value "1k")
      (footprint "eagle-import:R0603")
      (libsource (lib "eagle-import") (part "resistor_R-EU_R0603"))
    )
    (comp (ref "R27")
      (value "1k")
      (footprint "eagle-import:R0603")
      (libsource (lib "eagle-import") (part "resistor_R-EU_R0603"))
    )
    (comp (ref "R28")
      (value "10K")
      (footprint "eagle-import:R0603")
      (libsource (lib "eagle-import") (part "R-EU_R0603"))
    )
    (comp (ref "R29")
      (value "10K")
      (footprint "eagle-import:R0603")
      (libsource (lib "eagle-import") (part "R-EU_R0603"))
    )
    (comp (ref "R41")
      (value "120k")
      (footprint "eagle-import:R0603")
      (libsource (lib "eagle-import") (part "resistor_R-EU_R0603"))
    )
    (comp (ref "R42")
      (value "120k")
      (footprint "eagle-import:R0603")
      (libsource (lib "eagle-import") (part "resistor_R-EU_R0603"))
    )
    (comp (ref "R43")
      (value "120k")
      (footprint "eagle-import:R0603")
      (libsource (lib "eagle-import") (part "resistor_R-EU_R0603"))
    )
    (comp (ref "R51")
      (value "10k")
      (footprint "eagle-import:R0603")
      (libsource (lib "eagle-import") (part "resistor_R-EU_R0603"))
    )
    (comp (ref "R52")
      (value "10k")
      (footprint "eagle-import:R0603")
      (libsource (lib "eagle-import") (part "resistor_R-EU_R0603"))
    )
    (comp (ref "R53")
      (value "10k")
      (footprint "eagle-import:R0603")
      (libsource (lib "eagle-import") (part "resistor_R-EU_R0603"))
    )
    (comp (ref "RB1")
      (value "22r 0.3W 1%")
      (footprint "eagle-import:R1210")
      (libsource (lib "eagle-import") (part "R-EU_R1210"))
    )
    (comp (ref "RB1Q")
      (value "22r")
      (footprint "eagle-import:R1210")
      (libsource (lib "eagle-import") (part "R-EU_R1210"))
    )
    (comp (ref "RB1_")
      (value "22r 0.5W")
      (footprint "eagle-import:0207_7")
      (libsource (lib "eagle-import") (part "R-EU_0207/7"))
    )
    (comp (ref "RB2")
      (value "22r")
      (footprint "eagle-import:R1210")
      (libsource (lib "eagle-import") (part "R-EU_R1210"))
    )
    (comp (ref "RB2Q")
      (value "22r")
      (footprint "eagle-import:R1210")
      (libsource (lib "eagle-import") (part "R-EU_R1210"))
    )
    (comp (ref "RB2_")
      (value "22r")
      (footprint "eagle-import:0207_7")
      (libsource (lib "eagle-import") (part "R-EU_0207/7"))
    )
    (comp (ref "RB3")
      (value "22r")
      (footprint "eagle-import:R1210")
      (libsource (lib "eagle-import") (part "R-EU_R1210"))
    )
    (comp (ref "RB3Q")
      (value "22r")
      (footprint "eagle-import:R1210")
      (libsource (lib "eagle-import") (part "R-EU_R1210"))
    )
    (comp (ref "RB3_")
      (value "22r")
      (footprint "eagle-import:0207_7")
      (libsource (lib "eagle-import") (part "R-EU_0207/7"))
    )
    (comp (ref "RB4")
      (value "22r")
      (footprint "eagle-import:R1210")
      (libsource (lib "eagle-import") (part "R-EU_R1210"))
    )
    (comp (ref "RB4Q")
      (value "22r")
      (footprint "eagle-import:R1210")
      (libsource (lib "eagle-import") (part "R-EU_R1210"))
    )
    (comp (ref "RB4_")
      (value "22r")
      (footprint "eagle-import:0207_7")
      (libsource (lib "eagle-import") (part "R-EU_0207/7"))
    )
    (comp (ref "RB5")
      (value "22r")
      (footprint "eagle-import:R1210")
      (libsource (lib "eagle-import") (part "R-EU_R1210"))
    )
    (comp (ref "RB5Q")
      (value "22r")
      (footprint "eagle-import:R1210")
      (libsource (lib "eagle-import") (part "R-EU_R1210"))
    )
    (comp (ref "RB5_")
      (value "22r")
      (footprint "eagle-import:0207_7")
      (libsource (lib "eagle-import") (part "R-EU_0207/7"))
    )
    (comp (ref "RB6")
      (value "22r")
      (footprint "eagle-import:R1210")
      (libsource (lib "eagle-import") (part "R-EU_R1210"))
    )
    (comp (ref "RB6Q")
      (value "22r")
      (footprint "eagle-import:R1210")
      (libsource (lib "eagle-import") (part "R-EU_R1210"))
    )
    (comp (ref "RB6_")
      (value "22r")
      (footprint "eagle-import:0207_7")
      (libsource (lib "eagle-import") (part "R-EU_0207/7"))
    )
    (comp (ref "RB7")
      (value "22r")
      (footprint "eagle-import:R1210")
      (libsource (lib "eagle-import") (part "R-EU_R1210"))
    )
    (comp (ref "RB7Q")
      (value "22r")
      (footprint "eagle-import:R1210")
      (libsource (lib "eagle-import") (part "R-EU_R1210"))
    )
    (comp (ref "RB7_")
      (value "22r")
      (footprint "eagle-import:0207_7")
      (libsource (lib "eagle-import") (part "R-EU_0207/7"))
    )
    (comp (ref "RB8")
      (value "22r")
      (footprint "eagle-import:R1210")
      (libsource (lib "eagle-import") (part "R-EU_R1210"))
    )
    (comp (ref "RB8Q")
      (value "22r")
      (footprint "eagle-import:R1210")
      (libsource (lib "eagle-import") (part "R-EU_R1210"))
    )
    (comp (ref "RB8_")
      (value "22r")
      (footprint "eagle-import:0207_7")
      (libsource (lib "eagle-import") (part "R-EU_0207/7"))
    )
    (comp (ref "RB9")
      (value "100R 0.1%")
      (footprint "eagle-import:R1210")
      (libsource (lib "eagle-import") (part "R-EU_R1210"))
    )
    (comp (ref "RB9Q")
      (value "22R 0.1%")
      (footprint "eagle-import:R1210")
      (libsource (lib "eagle-import") (part "R-EU_R1210"))
    )
    (comp (ref "RB9_")
      (value "100R 0.1%")
      (footprint "eagle-import:0207_7")
      (libsource (lib "eagle-import") (part "R-EU_0207/7"))
    )
    (comp (ref "RF1")
      (value "9k1 0.1%")
      (footprint "eagle-import:R0603")
      (libsource (lib "eagle-import") (part "resistor_R-EU_R0603"))
    )
    (comp (ref "RF2")
      (value "9k1 0.1%")
      (footprint "eagle-import:R0603")
      (libsource (lib "eagle-import") (part "resistor_R-EU_R0603"))
    )
    (comp (ref "RF3")
      (value "9k1 0.1%")
      (footprint "eagle-import:R0603")
      (libsource (lib "eagle-import") (part "resistor_R-EU_R0603"))
    )
    (comp (ref "RF4")
      (value "9k1 0.1%")
      (footprint "eagle-import:R0603")
      (libsource (lib "eagle-import") (part "resistor_R-EU_R0603"))
    )
    (comp (ref "RF5")
      (value "9k1 0.1%")
      (footprint "eagle-import:R0603")
      (libsource (lib "eagle-import") (part "resistor_R-EU_R0603"))
    )
    (comp (ref "RF6")
      (value "9k1 0.1%")
      (footprint "eagle-import:R0603")
      (libsource (lib "eagle-import") (part "resistor_R-EU_R0603"))
    )
    (comp (ref "RF7")
      (value "9k1 0.1%")
      (footprint "eagle-import:R0603")
      (libsource (lib "eagle-import") (part "resistor_R-EU_R0603"))
    )
    (comp (ref "RF8")
      (value "9k1 0.1%")
      (footprint "eagle-import:R0603")
      (libsource (lib "eagle-import") (part "resistor_R-EU_R0603"))
    )
    (comp (ref "RF9")
      (value "9k1 0.1%")
      (footprint "eagle-import:R0603")
      (libsource (lib "eagle-import") (part "resistor_R-EU_R0603"))
    )
    (comp (ref "RFM69HCW")
      (value "RFM12_SMDSMD")
      (footprint "eagle-import:RFM12")
      (libsource (lib "eagle-import") (part "RFM12_SMDSMD"))
    )
    (comp (ref "RJ1")
      (value "95501-6889")
      (footprint "eagle-import:955016889")
      (fields (field (name "MOUSER_PART_NUMBER") "538-95501-6889") (field (name "RS_PART_NUMBER") "3862738"))
      (libsource (lib "eagle-import") (part "95501-6889"))
    )
    (comp (ref "RJ2")
      (value "95501-6889")
      (footprint "eagle-import:955016889")
      (fields (field (name "MOUSER_PART_NUMBER") "538-95501-6889") (field (name "RS_PART_NUMBER") "3862738"))
      (libsource (lib "eagle-import") (part "95501-6889"))
    )
    (comp (ref "S1")
      (value "31-XX")
      (footprint "eagle-import:B3F-31XX")
      (fields (field (name "MPN") "B3F-3100"))
      (libsource (lib "eagle-import") (part "31-XX"))
    )
    (comp (ref "S2")
      (value "KSS221GLFS")
      (footprint "eagle-import:KSS")
      (fields (field (name "RS_PART_NUMBER") "7931689P"))
      (libsource (lib "eagle-import") (part "KSS221GLFS"))
    )
    (comp (ref "SJ1")
      (value "SOLDERJUMPERNO")
      (footprint "eagle-import:SJ_2S-NO")
      (libsource (lib "eagle-import") (part "SOLDERJUMPERNO"))
    )
    (comp (ref "SJ2")
      (value "SOLDERJUMPERNO")
      (footprint "eagle-import:SJ_2S-NO")
      (libsource (lib "eagle-import") (part "SOLDERJUMPERNO"))
    )
    (comp (ref "SJ3")
      (value "SOLDERJUMPERNO")
      (footprint "eagle-import:SJ_2S-NO")
      (libsource (lib "eagle-import") (part "SOLDERJUMPERNO"))
    )
    (comp (ref "SJ4")
      (value "JUMPER-SMT_2_NO_SILK")
      (footprint "eagle-import:SMT-JUMPER_2_NO_SILK")
      (libsource (lib "eagle-import") (part "JUMPER-SMT_2_NO_SILK"))
    )
    (comp (ref "SJ5")
      (value "SOLDERJUMPERNO")
      (footprint "eagle-import:SJ_2S-NO")
      (libsource (lib "eagle-import") (part "SOLDERJUMPERNO"))
    )
    (comp (ref "SJ6")
      (value "SOLDERJUMPERNO")
      (footprint "eagle-import:SJ_2S-NO")
      (libsource (lib "eagle-import") (part "SOLDERJUMPERNO"))
    )
    (comp (ref "SJ7")
      (value "SOLDERJUMPERNO")
      (footprint "eagle-import:SJ_2S-NO")
      (libsource (lib "eagle-import") (part "SOLDERJUMPERNO"))
    )
    (comp (ref "SJ9")
      (value "JUMPER-SMT_2_NO_SILK")
      (footprint "eagle-import:SMT-JUMPER_2_NO_SILK")
      (libsource (lib "eagle-import") (part "JUMPER-SMT_2_NO_SILK"))
    )
    (comp (ref "SJ10")
      (value "JUMPER-SMT_2_NO_SILK")
      (footprint "eagle-import:SMT-JUMPER_2_NO_SILK")
      (libsource (lib "eagle-import") (part "JUMPER-SMT_2_NO_SILK"))
    )
    (comp (ref "SJ13")
      (value "JUMPER-SMT_2_NO_SILK")
      (footprint "eagle-import:SMT-JUMPER_2_NO_SILK")
      (libsource (lib "eagle-import") (part "JUMPER-SMT_2_NO_SILK"))
    )
    (comp (ref "SJ14")
      (value "SOLDERJUMPERNO")
      (footprint "eagle-import:SJ_2S-NO")
      (libsource (lib "eagle-import") (part "SOLDERJUMPERNO"))
    )
    (comp (ref "SJ20")
      (value "SOLDERJUMPERNO")
      (footprint "eagle-import:SJ_2S-NO")
      (libsource (lib "eagle-import") (part "SOLDERJUMPERNO"))
    )
    (comp (ref "SJ21")
      (value "SOLDERJUMPERNO")
      (footprint "eagle-import:SJ_2S-NO")
      (libsource (lib "eagle-import") (part "SOLDERJUMPERNO"))
    )
    (comp (ref "SJ23")
      (value "SOLDERJUMPERNO")
      (footprint "eagle-import:SJ_2S-NO")
      (libsource (lib "eagle-import") (part "SOLDERJUMPERNO"))
    )
    (comp (ref "SJ25")
      (value "SOLDERJUMPERNO")
      (footprint "eagle-import:SJ_2S-NO")
      (libsource (lib "eagle-import") (part "SOLDERJUMPERNO"))
    )
    (comp (ref "SJ26")
      (value "SOLDERJUMPERNO")
      (footprint "eagle-import:SJ_2S-NO")
      (libsource (lib "eagle-import") (part "SOLDERJUMPERNO"))
    )
    (comp (ref "SJ27")
      (value "SOLDERJUMPERNO")
      (footprint "eagle-import:SJ_2S-NO")
      (libsource (lib "eagle-import") (part "SOLDERJUMPERNO"))
    )
    (comp (ref "SJ32")
      (value "SOLDERJUMPERNO")
      (footprint "eagle-import:SJ_2S-NO")
      (libsource (lib "eagle-import") (part "SOLDERJUMPERNO"))
    )
    (comp (ref "SJ35")
      (value "SOLDERJUMPERNO")
      (footprint "eagle-import:SJ_2S-NO")
      (libsource (lib "eagle-import") (part "SOLDERJUMPERNO"))
    )
    (comp (ref "SJ36")
      (value "SOLDERJUMPERNO")
      (footprint "eagle-import:SJ_2S-NO")
      (libsource (lib "eagle-import") (part "SOLDERJUMPERNO"))
    )
    (comp (ref "SJ37")
      (value "SOLDERJUMPERNO")
      (footprint "eagle-import:SJ_2S-NO")
      (libsource (lib "eagle-import") (part "SOLDERJUMPERNO"))
    )
    (comp (ref "STM32F303VET6")
      (value "STM32F303VE")
      (footprint "eagle-import:TQFP100")
      (fields (field (name "MPN") "STM32F303VET6"))
      (libsource (lib "eagle-import") (part "STM32F303XB"))
    )
    (comp (ref "ST_LINK")
      (value "455-1750-1-ND")
      (footprint "eagle-import:1X03")
      (libsource (lib "eagle-import") (part "CONN_03"))
    )
    (comp (ref "SV1")
      (value "MA06-1")
      (footprint "eagle-import:MA06-1")
      (libsource (lib "eagle-import") (part "MA06-1"))
    )
    (comp (ref "SV2")
      (value "MA06-1")
      (footprint "eagle-import:MA06-1")
      (libsource (lib "eagle-import") (part "MA06-1"))
    )
    (comp (ref "TERM1")
      (value "3.5MM_TB_X6")
      (footprint "eagle-import:3.5MM_X6")
      (libsource (lib "eagle-import") (part "3.5MM_TB_X6"))
    )
    (comp (ref "TERM2")
      (value "3.5MM_TB_X6")
      (footprint "eagle-import:3.5MM_X6")
      (libsource (lib "eagle-import") (part "3.5MM_TB_X6"))
    )
    (comp (ref "TERM3")
      (value "3.5MM_TB_X6")
      (footprint "eagle-import:3.5MM_X6")
      (libsource (lib "eagle-import") (part "3.5MM_TB_X6"))
    )
    (comp (ref "TP1")
      (value "TEST-POINT3")
      (footprint "eagle-import:PAD.03X.03")
      (libsource (lib "eagle-import") (part "TEST-POINT3"))
    )
    (comp (ref "TP2")
      (value "TEST-POINT3")
      (footprint "eagle-import:PAD.03X.03")
      (libsource (lib "eagle-import") (part "TEST-POINT3"))
    )
    (comp (ref "TP3")
      (value "TEST-POINT3")
      (footprint "eagle-import:PAD.03X.03")
      (libsource (lib "eagle-import") (part "TEST-POINT3"))
    )
    (comp (ref "TP4")
      (value "TPB1,27")
      (footprint "eagle-import:B1,27")
      (libsource (lib "eagle-import") (part "TPB1,27"))
    )
    (comp (ref "TP5")
      (value "TEST-POINTPOGO_PTH")
      (footprint "eagle-import:1X01_NO_SILK")
      (libsource (lib "eagle-import") (part "TEST-POINTPOGO_PTH"))
    )
    (comp (ref "TP6")
      (value "TEST-POINTPOGO_PTH")
      (footprint "eagle-import:1X01_NO_SILK")
      (libsource (lib "eagle-import") (part "TEST-POINTPOGO_PTH"))
    )
    (comp (ref "TP7")
      (value "TEST-POINTPOGO_PTH")
      (footprint "eagle-import:1X01_NO_SILK")
      (libsource (lib "eagle-import") (part "TEST-POINTPOGO_PTH"))
    )
    (comp (ref "TP9")
      (value "TEST-POINTPOGO_PTH")
      (footprint "eagle-import:1X01_NO_SILK")
      (libsource (lib "eagle-import") (part "TEST-POINTPOGO_PTH"))
    )
    (comp (ref "TP10")
      (value "TEST-POINTPOGO_PTH")
      (footprint "eagle-import:1X01_NO_SILK")
      (libsource (lib "eagle-import") (part "TEST-POINTPOGO_PTH"))
    )
    (comp (ref "TP11")
      (value "TEST-POINT3")
      (footprint "eagle-import:PAD.03X.03")
      (libsource (lib "eagle-import") (part "TEST-POINT3"))
    )
    (comp (ref "TP12")
      (value "TEST-POINT3")
      (footprint "eagle-import:PAD.03X.03")
      (libsource (lib "eagle-import") (part "TEST-POINT3"))
    )
    (comp (ref "TP13")
      (value "TEST-POINT3")
      (footprint "eagle-import:PAD.03X.03")
      (libsource (lib "eagle-import") (part "TEST-POINT3"))
    )
    (comp (ref "TP14")
      (value "TEST-POINT3")
      (footprint "eagle-import:PAD.03X.03")
      (libsource (lib "eagle-import") (part "TEST-POINT3"))
    )
    (comp (ref "TP15")
      (value "TEST-POINT3")
      (footprint "eagle-import:PAD.03X.03")
      (libsource (lib "eagle-import") (part "TEST-POINT3"))
    )
    (comp (ref "TP16")
      (value "TEST-POINT3")
      (footprint "eagle-import:PAD.03X.03")
      (libsource (lib "eagle-import") (part "TEST-POINT3"))
    )
    (comp (ref "TP17")
      (value "TEST-POINTPOGO_PTH")
      (footprint "eagle-import:1X01_NO_SILK")
      (libsource (lib "eagle-import") (part "TEST-POINTPOGO_PTH"))
    )
    (comp (ref "TP18")
      (value "TEST-POINTPOGO_PTH")
      (footprint "eagle-import:1X01_NO_SILK")
      (libsource (lib "eagle-import") (part "TEST-POINTPOGO_PTH"))
    )
    (comp (ref "TP19")
      (value "TEST-POINTPOGO_PTH")
      (footprint "eagle-import:1X01_NO_SILK")
      (libsource (lib "eagle-import") (part "TEST-POINTPOGO_PTH"))
    )
    (comp (ref "TP20")
      (value "TEST-POINTPOGO_PTH")
      (footprint "eagle-import:1X01_NO_SILK")
      (libsource (lib "eagle-import") (part "TEST-POINTPOGO_PTH"))
    )
    (comp (ref "TP21")
      (value "TEST-POINT3")
      (footprint "eagle-import:PAD.03X.03")
      (libsource (lib "eagle-import") (part "TEST-POINT3"))
    )
    (comp (ref "U$2")
      (value "BOOST_MODULE")
      (footprint "eagle-import:BOOST")
      (libsource (lib "eagle-import") (part "BOOST_MODULE"))
    )
    (comp (ref "U$7")
      (value "47219-2001_MICROSD")
      (footprint "eagle-import:47219-2001_MICROSD")
      (libsource (lib "eagle-import") (part "47219-2001_MICROSD"))
    )
    (comp (ref "U1")
      (value "ESP32-WROOM-32D")
      (footprint "eagle-import:MODULE_ESP32-WROOM-32D")
      (fields (field (name "MF") "Espressif Systems"))
      (libsource (lib "eagle-import") (part "ESP32-WROOM-32D"))
    )
    (comp (ref "UART1")
      (value "M02PTH")
      (footprint "eagle-import:1X02")
      (libsource (lib "eagle-import") (part "M02PTH"))
    )
    (comp (ref "UART_STM")
      (value "MA06-1")
      (footprint "eagle-import:MA06-1")
      (libsource (lib "eagle-import") (part "MA06-1"))
    )
    (comp (ref "USB-C")
      (value "CSP-USC16-TR")
      (footprint "eagle-import:USB-C")
      (libsource (lib "eagle-import") (part "CSP-USC16-TR"))
    )
    (comp (ref "VT1")
      (value "ADC-028-2-T")
      (footprint "eagle-import:DCJACK_2MM_SMT")
      (fields (field (name "MPN") "ADC-028-1-T"))
      (libsource (lib "eagle-import") (part "2.1MMJACKSMT"))
    )
  )
  (nets
    (net (code "1") (name "+3V3") (class "Default")
      (node (ref "BOOT_STM") (pin "2") (pinfunction "2_2") (pintype "passive"))
      (node (ref "C13") (pin "1") (pinfunction "1_1") (pintype "passive"))
      (node (ref "C14") (pin "1") (pinfunction "1_1") (pintype "passive"))
      (node (ref "C17") (pin "1") (pinfunction "1_1") (pintype "passive"))
      (node (ref "C2") (pin "1") (pinfunction "1_1") (pintype "passive"))
      (node (ref "C24") (pin "1") (pinfunction "1_1") (pintype "passive"))
      (node (ref "C25") (pin "1") (pinfunction "1_1") (pintype "passive"))
      (node (ref "C26") (pin "1") (pinfunction "1_1") (pintype "passive"))
      (node (ref "C33") (pin "1") (pinfunction "1_1") (pintype "passive"))
      (node (ref "C4") (pin "2") (pinfunction "2_2") (pintype "passive"))
      (node (ref "C40") (pin "1") (pinfunction "1_1") (pintype "passive"))
      (node (ref "C45") (pin "1") (pinfunction "1_1") (pintype "passive"))
      (node (ref "C5") (pin "2") (pinfunction "2_2") (pintype "passive"))
      (node (ref "C6") (pin "2") (pinfunction "2_2") (pintype "passive"))
      (node (ref "C8") (pin "2") (pinfunction "2_2") (pintype "passive"))
      (node (ref "C9") (pin "2") (pinfunction "2_2") (pintype "passive"))
      (node (ref "D1") (pin "K") (pinfunction "C_K") (pintype "passive"))
      (node (ref "D15") (pin "K") (pinfunction "C_K") (pintype "passive"))
      (node (ref "D16") (pin "K") (pinfunction "C_K") (pintype "passive"))
      (node (ref "D19") (pin "K") (pinfunction "C_K") (pintype "passive"))
      (node (ref "D20") (pin "K") (pinfunction "C_K") (pintype "passive"))
      (node (ref "D21") (pin "K") (pinfunction "C_K") (pintype "passive"))
      (node (ref "D22") (pin "K") (pinfunction "C_K") (pintype "passive"))
      (node (ref "D23") (pin "K") (pinfunction "C_K") (pintype "passive"))
      (node (ref "D24") (pin "K") (pinfunction "C_K") (pintype "passive"))
      (node (ref "D25") (pin "K") (pinfunction "C_K") (pintype "passive"))
      (node (ref "D27") (pin "K") (pinfunction "C_K") (pintype "passive"))
      (node (ref "D28") (pin "K") (pinfunction "C_K") (pintype "passive"))
      (node (ref "D29") (pin "K") (pinfunction "C_K") (pintype "passive"))
      (node (ref "D30") (pin "K") (pinfunction "C_K") (pintype "passive"))
      (node (ref "D31") (pin "K") (pinfunction "C_K") (pintype "passive"))
      (node (ref "D32") (pin "K") (pinfunction "C_K") (pintype "passive"))
      (node (ref "D34") (pin "K") (pinfunction "C_K") (pintype "passive"))
      (node (ref "EXPANSION") (pin "24") (pinfunction "24_24") (pintype "passive"))
      (node (ref "EXPANSION") (pin "4") (pinfunction "4_4") (pintype "passive"))
      (node (ref "JP1") (pin "1") (pinfunction "1_1") (pintype "passive"))
      (node (ref "MCP1825") (pin "3") (pinfunction "+3V3_3") (pintype "power_in"))
      (node (ref "OLED") (pin "3") (pinfunction "3_3") (pintype "passive"))
      (node (ref "Q4") (pin "3") (pinfunction "D_3") (pintype "passive"))
      (node (ref "R1") (pin "2") (pinfunction "2_2") (pintype "passive"))
      (node (ref "R10") (pin "2") (pinfunction "2_2") (pintype "passive"))
      (node (ref "R13") (pin "1") (pinfunction "1_1") (pintype "passive"))
      (node (ref "R20") (pin "1") (pinfunction "1_1") (pintype "passive"))
      (node (ref "R7") (pin "2") (pinfunction "2_2") (pintype "passive"))
      (node (ref "RFM69HCW") (pin "9") (pinfunction "VDD_9") (pintype "power_in"))
      (node (ref "RJ1") (pin "2") (pinfunction "2_2") (pintype "bidirectional"))
      (node (ref "RJ2") (pin "2") (pinfunction "2_2") (pintype "bidirectional"))
      (node (ref "SJ1") (pin "2") (pinfunction "2_2") (pintype "passive"))
      (node (ref "SJ2") (pin "2") (pinfunction "2_2") (pintype "passive"))
      (node (ref "SJ23") (pin "2") (pinfunction "2_2") (pintype "passive"))
      (node (ref "STM32F303VET6") (pin "100") (pinfunction "VDD_100") (pintype "bidirectional"))
      (node (ref "STM32F303VET6") (pin "22") (pinfunction "VDDA_22") (pintype "bidirectional"))
      (node (ref "STM32F303VET6") (pin "28") (pinfunction "VDD_28") (pintype "bidirectional"))
      (node (ref "STM32F303VET6") (pin "50") (pinfunction "VDD_50") (pintype "bidirectional"))
      (node (ref "STM32F303VET6") (pin "75") (pinfunction "VDD_75") (pintype "bidirectional"))
      (node (ref "TERM1") (pin "P$1") (pinfunction "P$1_P$1") (pintype "bidirectional"))
      (node (ref "TERM2") (pin "P$5") (pinfunction "P$5_P$5") (pintype "bidirectional"))
      (node (ref "TERM3") (pin "P$5") (pinfunction "P$5_P$5") (pintype "bidirectional"))
      (node (ref "U$7") (pin "PIN4") (pinfunction "VDD_PIN4") (pintype "bidirectional"))
      (node (ref "UART_STM") (pin "2") (pinfunction "2_2") (pintype "passive"))
    )
    (net (code "2") (name "+5V") (class "Default")
      (node (ref "C10") (pin "1") (pinfunction "1_1") (pintype "passive"))
      (node (ref "C11") (pin "1") (pinfunction "1_1") (pintype "passive"))
      (node (ref "C12") (pin "2") (pinfunction "2_2") (pintype "passive"))
      (node (ref "C15") (pin "2") (pinfunction "2_2") (pintype "passive"))
      (node (ref "C18") (pin "1") (pinfunction "1_1") (pintype "passive"))
      (node (ref "C21") (pin "1") (pinfunction "1_1") (pintype "passive"))
      (node (ref "C27") (pin "1") (pinfunction "1_1") (pintype "passive"))
      (node (ref "C28") (pin "1") (pinfunction "1_1") (pintype "passive"))
      (node (ref "C3") (pin "1") (pinfunction "1_1") (pintype "passive"))
      (node (ref "C42") (pin "1") (pinfunction "1_1") (pintype "passive"))
      (node (ref "C47") (pin "1") (pinfunction "1_1") (pintype "passive"))
      (node (ref "C7") (pin "1") (pinfunction "1_1") (pintype "passive"))
      (node (ref "D40*1") (pin "K") (pinfunction "C_K") (pintype "passive"))
      (node (ref "EXPANSION") (pin "26") (pinfunction "26_26") (pintype "passive"))
      (node (ref "FB1") (pin "2") (pinfunction "P$2_2") (pintype "passive"))
      (node (ref "MCP1825") (pin "1") (pinfunction "IN_1") (pintype "power_in"))
      (node (ref "PCB2") (pin "P$42") (pinfunction "5V_P$42") (pintype "bidirectional"))
      (node (ref "PCB2") (pin "P$44") (pinfunction "5V_P$44") (pintype "bidirectional"))
      (node (ref "PS1") (pin "2") (pinfunction "VIN_2") (pintype "output"))
      (node (ref "RJ1") (pin "7") (pinfunction "7_7") (pintype "bidirectional"))
      (node (ref "RJ2") (pin "7") (pinfunction "7_7") (pintype "bidirectional"))
      (node (ref "SV1") (pin "3") (pinfunction "3_3") (pintype "passive"))
      (node (ref "SV2") (pin "3") (pinfunction "3_3") (pintype "passive"))
      (node (ref "TERM2") (pin "P$6") (pinfunction "P$6_P$6") (pintype "bidirectional"))
      (node (ref "TP4") (pin "TP") (pinfunction "TP_TP") (pintype "input"))
      (node (ref "U$2") (pin "IN+") (pinfunction "+5V_IN+") (pintype "bidirectional"))
      (node (ref "UART_STM") (pin "3") (pinfunction "3_3") (pintype "passive"))
    )
    (net (code "3") (name "/+24V") (class "Default")
      (node (ref "R11") (pin "2") (pinfunction "2_2") (pintype "passive"))
      (node (ref "R17") (pin "2") (pinfunction "2_2") (pintype "passive"))
      (node (ref "R9") (pin "2") (pinfunction "2_2") (pintype "passive"))
      (node (ref "TERM2") (pin "P$1") (pinfunction "P$1_P$1") (pintype "bidirectional"))
      (node (ref "U$2") (pin "OUT+") (pinfunction "24V_OUT+") (pintype "bidirectional"))
    )
    (net (code "4") (name "/AC1") (class "Default")
      (node (ref "Q21") (pin "3") (pinfunction "D_3") (pintype "bidirectional"))
      (node (ref "R43") (pin "2") (pinfunction "2_2") (pintype "passive"))
      (node (ref "SJ37") (pin "2") (pinfunction "2_2") (pintype "passive"))
      (node (ref "TERM3") (pin "P$2") (pinfunction "P$2_P$2") (pintype "bidirectional"))
      (node (ref "VT1") (pin "PWR2") (pinfunction "TIP_PWR2") (pintype "bidirectional"))
    )
    (net (code "5") (name "/AC1_MOS") (class "Default")
      (node (ref "Q21") (pin "2") (pinfunction "S_2") (pintype "bidirectional"))
      (node (ref "R25") (pin "1") (pinfunction "1_1") (pintype "passive"))
      (node (ref "R43") (pin "1") (pinfunction "1_1") (pintype "passive"))
      (node (ref "R53") (pin "1") (pinfunction "1_1") (pintype "passive"))
      (node (ref "SJ37") (pin "1") (pinfunction "1_1") (pintype "passive"))
    )
    (net (code "6") (name "/AC2") (class "Default")
      (node (ref "Q22") (pin "3") (pinfunction "D_3") (pintype "bidirectional"))
      (node (ref "R42") (pin "2") (pinfunction "2_2") (pintype "passive"))
      (node (ref "SJ36") (pin "2") (pinfunction "2_2") (pintype "passive"))
      (node (ref "TERM3") (pin "P$3") (pinfunction "P$3_P$3") (pintype "bidirectional"))
    )
    (net (code "7") (name "/AC2_MOS") (class "Default")
      (node (ref "Q22") (pin "2") (pinfunction "S_2") (pintype "bidirectional"))
      (node (ref "R26") (pin "1") (pinfunction "1_1") (pintype "passive"))
      (node (ref "R42") (pin "1") (pinfunction "1_1") (pintype "passive"))
      (node (ref "R52") (pin "1") (pinfunction "1_1") (pintype "passive"))
      (node (ref "SJ36") (pin "1") (pinfunction "1_1") (pintype "passive"))
    )
    (net (code "8") (name "/AC3") (class "Default")
      (node (ref "Q33") (pin "3") (pinfunction "D_3") (pintype "bidirectional"))
      (node (ref "R41") (pin "1") (pinfunction "1_1") (pintype "passive"))
      (node (ref "SJ35") (pin "2") (pinfunction "2_2") (pintype "passive"))
      (node (ref "TERM3") (pin "P$4") (pinfunction "P$4_P$4") (pintype "bidirectional"))
    )
    (net (code "9") (name "/AC3_MOS") (class "Default")
      (node (ref "Q33") (pin "2") (pinfunction "S_2") (pintype "bidirectional"))
      (node (ref "R27") (pin "1") (pinfunction "1_1") (pintype "passive"))
      (node (ref "R41") (pin "2") (pinfunction "2_2") (pintype "passive"))
      (node (ref "R51") (pin "1") (pinfunction "1_1") (pintype "passive"))
      (node (ref "SJ35") (pin "1") (pinfunction "1_1") (pintype "passive"))
    )
    (net (code "10") (name "/BIAS*") (class "Default")
      (node (ref "R6") (pin "2") (pinfunction "2_2") (pintype "passive"))
      (node (ref "STM32F303VET6") (pin "51") (pinfunction "PB12_51") (pintype "bidirectional"))
    )
    (net (code "11") (name "/CT_EX1") (class "Default")
      (node (ref "EXPANSION") (pin "3") (pinfunction "3_3") (pintype "passive"))
    )
    (net (code "12") (name "/CT_EX2") (class "Default")
      (node (ref "EXPANSION") (pin "6") (pinfunction "6_6") (pintype "passive"))
    )
    (net (code "13") (name "/CT_EX3") (class "Default")
      (node (ref "EXPANSION") (pin "5") (pinfunction "5_5") (pintype "passive"))
    )
    (net (code "14") (name "/CT_EX4") (class "Default")
      (node (ref "EXPANSION") (pin "8") (pinfunction "8_8") (pintype "passive"))
    )
    (net (code "15") (name "/CT_EX5") (class "Default")
      (node (ref "EXPANSION") (pin "7") (pinfunction "7_7") (pintype "passive"))
    )
    (net (code "16") (name "/CT_EX6") (class "Default")
      (node (ref "EXPANSION") (pin "10") (pinfunction "10_10") (pintype "passive"))
    )
    (net (code "17") (name "/IO1_EX") (class "Default")
      (node (ref "EXPANSION") (pin "15") (pinfunction "15_15") (pintype "passive"))
    )
    (net (code "18") (name "/IO2_EX") (class "Default")
      (node (ref "EXPANSION") (pin "16") (pinfunction "16_16") (pintype "passive"))
    )
    (net (code "19") (name "/IO3_EX") (class "Default")
      (node (ref "EXPANSION") (pin "17") (pinfunction "17_17") (pintype "passive"))
    )
    (net (code "20") (name "/IO4_EX") (class "Default")
      (node (ref "EXPANSION") (pin "18") (pinfunction "18_18") (pintype "passive"))
    )
    (net (code "21") (name "/IO5_EX") (class "Default")
      (node (ref "EXPANSION") (pin "19") (pinfunction "19_19") (pintype "passive"))
    )
    (net (code "22") (name "/IO6_EX") (class "Default")
      (node (ref "EXPANSION") (pin "21") (pinfunction "21_21") (pintype "passive"))
    )
    (net (code "23") (name "/IO7_EX") (class "Default")
      (node (ref "EXPANSION") (pin "23") (pinfunction "23_23") (pintype "passive"))
    )
    (net (code "24") (name "/MBUS_I{slash}O") (class "Default")
      (node (ref "Q1") (pin "2") (pinfunction "E_2") (pintype "passive"))
      (node (ref "R17") (pin "1") (pinfunction "1_1") (pintype "passive"))
      (node (ref "TERM2") (pin "P$2") (pinfunction "P$2_P$2") (pintype "bidirectional"))
    )
    (net (code "25") (name "/PC14") (class "Default")
      (node (ref "C31") (pin "1") (pinfunction "1_1") (pintype "passive"))
      (node (ref "LSE") (pin "P$1") (pinfunction "1_P$1") (pintype "passive"))
      (node (ref "STM32F303VET6") (pin "8") (pinfunction "PC14/OSC32_IN_8") (pintype "bidirectional"))
    )
    (net (code "26") (name "/PC15") (class "Default")
      (node (ref "C32") (pin "1") (pinfunction "1_1") (pintype "passive"))
      (node (ref "LSE") (pin "P$4") (pinfunction "2_P$4") (pintype "passive"))
      (node (ref "STM32F303VET6") (pin "9") (pinfunction "PC15/OSC32_OUT_9") (pintype "bidirectional"))
    )
    (net (code "27") (name "/RPI_MISO") (class "Default")
      (node (ref "PCB2") (pin "P$61") (pinfunction "GPIO9_P$61") (pintype "bidirectional"))
      (node (ref "SJ6") (pin "2") (pinfunction "2_2") (pintype "passive"))
    )
    (net (code "28") (name "/RPI_MOSI") (class "Default")
      (node (ref "PCB2") (pin "P$59") (pinfunction "GPIO10_P$59") (pintype "bidirectional"))
      (node (ref "SJ5") (pin "2") (pinfunction "2_2") (pintype "passive"))
    )
    (net (code "29") (name "/RPI_SPI_CLK") (class "Default")
      (node (ref "PCB2") (pin "P$63") (pinfunction "GPIO11_P$63") (pintype "bidirectional"))
      (node (ref "SJ7") (pin "2") (pinfunction "2_2") (pintype "passive"))
    )
    (net (code "30") (name "/RXD0_ESP") (class "Default")
      (node (ref "SJ21") (pin "2") (pinfunction "2_2") (pintype "passive"))
      (node (ref "SV2") (pin "4") (pinfunction "4_4") (pintype "passive"))
      (node (ref "U1") (pin "34") (pinfunction "RXD0_34") (pintype "bidirectional"))
    )
    (net (code "31") (name "/SD_CLK") (class "Default")
      (node (ref "JP8") (pin "2") (pinfunction "2_2") (pintype "passive"))
      (node (ref "U$7") (pin "PIN5") (pinfunction "CLK_PIN5") (pintype "bidirectional"))
    )
    (net (code "32") (name "/SD_CS_") (class "Default")
      (node (ref "JP2") (pin "2") (pinfunction "2_2") (pintype "passive"))
      (node (ref "U$7") (pin "PIN2") (pinfunction "CD/DAT3_PIN2") (pintype "bidirectional"))
    )
    (net (code "33") (name "/SD_MISO") (class "Default")
      (node (ref "JP7") (pin "2") (pinfunction "2_2") (pintype "passive"))
      (node (ref "U$7") (pin "PIN7") (pinfunction "DAT0_PIN7") (pintype "bidirectional"))
    )
    (net (code "34") (name "/SD_MOSI") (class "Default")
      (node (ref "JP3") (pin "2") (pinfunction "2_2") (pintype "passive"))
      (node (ref "U$7") (pin "PIN3") (pinfunction "CMD_PIN3") (pintype "bidirectional"))
    )
    (net (code "35") (name "/TXD0_ESP") (class "Default")
      (node (ref "SJ20") (pin "2") (pinfunction "2_2") (pintype "passive"))
      (node (ref "SV2") (pin "5") (pinfunction "5_5") (pintype "passive"))
      (node (ref "U1") (pin "35") (pinfunction "TXD0_35") (pintype "bidirectional"))
    )
    (net (code "36") (name "ADC_2_RJ45IN") (class "Default")
      (node (ref "RJ2") (pin "8") (pinfunction "8_8") (pintype "bidirectional"))
      (node (ref "STM32F303VET6") (pin "61") (pinfunction "PD14_61") (pintype "bidirectional"))
    )
    (net (code "37") (name "ADC_RJ45IN") (class "Default")
      (node (ref "RJ1") (pin "8") (pinfunction "8_8") (pintype "bidirectional"))
      (node (ref "STM32F303VET6") (pin "54") (pinfunction "PB15_54") (pintype "bidirectional"))
    )
    (net (code "38") (name "BIAS") (class "Default")
      (node (ref "CT1") (pin "P$1") (pinfunction "1_P$1") (pintype "bidirectional"))
      (node (ref "CT2") (pin "P$1") (pinfunction "1_P$1") (pintype "bidirectional"))
      (node (ref "CT3") (pin "P$1") (pinfunction "1_P$1") (pintype "bidirectional"))
      (node (ref "CT4") (pin "P$1") (pinfunction "1_P$1") (pintype "bidirectional"))
      (node (ref "CT4") (pin "P$4") (pinfunction "4_P$4") (pintype "bidirectional"))
      (node (ref "CT5") (pin "P$1") (pinfunction "1_P$1") (pintype "bidirectional"))
      (node (ref "CT5") (pin "P$4") (pinfunction "4_P$4") (pintype "bidirectional"))
      (node (ref "CT6") (pin "P$1") (pinfunction "1_P$1") (pintype "bidirectional"))
      (node (ref "CT6") (pin "P$4") (pinfunction "4_P$4") (pintype "bidirectional"))
      (node (ref "CT7") (pin "P$1") (pinfunction "1_P$1") (pintype "bidirectional"))
      (node (ref "CT7") (pin "P$4") (pinfunction "4_P$4") (pintype "bidirectional"))
      (node (ref "CT8") (pin "P$1") (pinfunction "1_P$1") (pintype "bidirectional"))
      (node (ref "CT8") (pin "P$4") (pinfunction "4_P$4") (pintype "bidirectional"))
      (node (ref "CT9") (pin "P$1") (pinfunction "1_P$1") (pintype "bidirectional"))
      (node (ref "CT9") (pin "P$4") (pinfunction "4_P$4") (pintype "bidirectional"))
      (node (ref "D1") (pin "A") (pinfunction "A_A") (pintype "passive"))
      (node (ref "D14") (pin "K") (pinfunction "C_K") (pintype "passive"))
      (node (ref "JP4") (pin "2") (pinfunction "2_2") (pintype "passive"))
      (node (ref "JP5") (pin "2") (pinfunction "2_2") (pintype "passive"))
      (node (ref "JP6") (pin "2") (pinfunction "2_2") (pintype "passive"))
      (node (ref "R51") (pin "2") (pinfunction "2_2") (pintype "passive"))
      (node (ref "R52") (pin "2") (pinfunction "2_2") (pintype "passive"))
      (node (ref "R53") (pin "2") (pinfunction "2_2") (pintype "passive"))
      (node (ref "R6") (pin "1") (pinfunction "1_1") (pintype "passive"))
      (node (ref "RB4") (pin "2") (pinfunction "2_2") (pintype "passive"))
      (node (ref "RB4Q") (pin "1") (pinfunction "1_1") (pintype "passive"))
      (node (ref "RB4_") (pin "2") (pinfunction "2_2") (pintype "passive"))
      (node (ref "RB5") (pin "2") (pinfunction "2_2") (pintype "passive"))
      (node (ref "RB5Q") (pin "1") (pinfunction "1_1") (pintype "passive"))
      (node (ref "RB5_") (pin "2") (pinfunction "2_2") (pintype "passive"))
      (node (ref "RB6") (pin "2") (pinfunction "2_2") (pintype "passive"))
      (node (ref "RB6Q") (pin "1") (pinfunction "1_1") (pintype "passive"))
      (node (ref "RB6_") (pin "2") (pinfunction "2_2") (pintype "passive"))
      (node (ref "RB7") (pin "2") (pinfunction "2_2") (pintype "passive"))
      (node (ref "RB7Q") (pin "1") (pinfunction "1_1") (pintype "passive"))
      (node (ref "RB7_") (pin "2") (pinfunction "2_2") (pintype "passive"))
      (node (ref "RB8") (pin "2") (pinfunction "2_2") (pintype "passive"))
      (node (ref "RB8Q") (pin "1") (pinfunction "1_1") (pintype "passive"))
      (node (ref "RB8_") (pin "2") (pinfunction "2_2") (pintype "passive"))
      (node (ref "RB9") (pin "2") (pinfunction "2_2") (pintype "passive"))
      (node (ref "RB9Q") (pin "1") (pinfunction "1_1") (pintype "passive"))
      (node (ref "RB9_") (pin "2") (pinfunction "2_2") (pintype "passive"))
      (node (ref "TERM3") (pin "P$1") (pinfunction "P$1_P$1") (pintype "bidirectional"))
      (node (ref "TP5") (pin "1") (pinfunction "1_1") (pintype "bidirectional"))
      (node (ref "VT1") (pin "GND") (pinfunction "RING_GND") (pintype "bidirectional"))
      (node (ref "VT1") (pin "GNDBREAK") (pinfunction "RING_SW_GNDBREAK") (pintype "bidirectional"))
    )
    (net (code "39") (name "BIAS_IN") (class "Default")
      (node (ref "C50*") (pin "2") (pinfunction "2_2") (pintype "passive"))
      (node (ref "R22") (pin "1") (pinfunction "1_1") (pintype "passive"))
      (node (ref "R23") (pin "2") (pinfunction "2_2") (pintype "passive"))
      (node (ref "STM32F303VET6") (pin "58") (pinfunction "PD11_58") (pintype "bidirectional"))
      (node (ref "TP10") (pin "1") (pinfunction "1_1") (pintype "bidirectional"))
    )
    (net (code "40") (name "BOOT0") (class "Default")
      (node (ref "BOOT_STM") (pin "1") (pinfunction "1_1") (pintype "passive"))
      (node (ref "J1") (pin "1") (pinfunction "1_1") (pintype "passive"))
      (node (ref "R2") (pin "1") (pinfunction "1_1") (pintype "passive"))
      (node (ref "STM32F303VET6") (pin "94") (pinfunction "BOOT0_94") (pintype "bidirectional"))
    )
    (net (code "41") (name "BUTTON1") (class "Default")
      (node (ref "PCB2") (pin "P$53") (pinfunction "GPIO27_P$53") (pintype "bidirectional"))
      (node (ref "S1") (pin "2") (pinfunction "S_2") (pintype "passive"))
      (node (ref "SJ3") (pin "1") (pinfunction "1_1") (pintype "passive"))
    )
    (net (code "42") (name "CT1") (class "Default")
      (node (ref "CF1") (pin "2") (pinfunction "2_2") (pintype "passive"))
      (node (ref "RF1") (pin "2") (pinfunction "2_2") (pintype "passive"))
      (node (ref "STM32F303VET6") (pin "18") (pinfunction "PC3_18") (pintype "bidirectional"))
      (node (ref "TP18") (pin "1") (pinfunction "1_1") (pintype "bidirectional"))
    )
    (net (code "43") (name "CT2") (class "Default")
      (node (ref "CF2") (pin "2") (pinfunction "2_2") (pintype "passive"))
      (node (ref "RF2") (pin "2") (pinfunction "2_2") (pintype "passive"))
      (node (ref "STM32F303VET6") (pin "29") (pinfunction "PA4_29") (pintype "bidirectional"))
    )
    (net (code "44") (name "CT3") (class "Default")
      (node (ref "CF3") (pin "2") (pinfunction "2_2") (pintype "passive"))
      (node (ref "RF3") (pin "2") (pinfunction "2_2") (pintype "passive"))
      (node (ref "STM32F303VET6") (pin "30") (pinfunction "PA5_30") (pintype "bidirectional"))
    )
    (net (code "45") (name "CT4") (class "Default")
      (node (ref "CF4") (pin "2") (pinfunction "2_2") (pintype "passive"))
      (node (ref "RF4") (pin "2") (pinfunction "2_2") (pintype "passive"))
      (node (ref "STM32F303VET6") (pin "31") (pinfunction "PA6_31") (pintype "bidirectional"))
    )
    (net (code "46") (name "CT5") (class "Default")
      (node (ref "CF5") (pin "2") (pinfunction "2_2") (pintype "passive"))
      (node (ref "RF5") (pin "2") (pinfunction "2_2") (pintype "passive"))
      (node (ref "STM32F303VET6") (pin "32") (pinfunction "PA7_32") (pintype "bidirectional"))
    )
    (net (code "47") (name "CT6") (class "Default")
      (node (ref "CF6") (pin "2") (pinfunction "2_2") (pintype "passive"))
      (node (ref "RF6") (pin "2") (pinfunction "2_2") (pintype "passive"))
      (node (ref "STM32F303VET6") (pin "33") (pinfunction "PC4_33") (pintype "bidirectional"))
    )
    (net (code "48") (name "CT7") (class "Default")
      (node (ref "CF7") (pin "2") (pinfunction "2_2") (pintype "passive"))
      (node (ref "RF7") (pin "2") (pinfunction "2_2") (pintype "passive"))
      (node (ref "STM32F303VET6") (pin "34") (pinfunction "PC5_34") (pintype "bidirectional"))
      (node (ref "TP19") (pin "1") (pinfunction "1_1") (pintype "bidirectional"))
    )
    (net (code "49") (name "CT8") (class "Default")
      (node (ref "CF8") (pin "2") (pinfunction "2_2") (pintype "passive"))
      (node (ref "RF8") (pin "2") (pinfunction "2_2") (pintype "passive"))
      (node (ref "STM32F303VET6") (pin "37") (pinfunction "PB2_37") (pintype "bidirectional"))
    )
    (net (code "50") (name "CT9") (class "Default")
      (node (ref "CF9") (pin "2") (pinfunction "2_2") (pintype "passive"))
      (node (ref "RF9") (pin "2") (pinfunction "2_2") (pintype "passive"))
      (node (ref "STM32F303VET6") (pin "48") (pinfunction "PB11_48") (pintype "bidirectional"))
    )
    (net (code "51") (name "DIO0_RFM") (class "Default")
      (node (ref "RFM69HCW") (pin "2") (pinfunction "~{IRQ}_2") (pintype "output"))
      (node (ref "STM32F303VET6") (pin "98") (pinfunction "PE1_98") (pintype "bidirectional"))
    )
    (net (code "52") (name "DS18B20_RJ45") (class "Default")
      (node (ref "R1") (pin "1") (pinfunction "1_1") (pintype "passive"))
      (node (ref "R7") (pin "1") (pinfunction "1_1") (pintype "passive"))
      (node (ref "RJ1") (pin "4") (pinfunction "4_4") (pintype "bidirectional"))
      (node (ref "RJ2") (pin "4") (pinfunction "4_4") (pintype "bidirectional"))
      (node (ref "STM32F303VET6") (pin "78") (pinfunction "PC10_78") (pintype "bidirectional"))
      (node (ref "TP9") (pin "1") (pinfunction "1_1") (pintype "bidirectional"))
    )
    (net (code "53") (name "ESP_PWR") (class "Default")
      (node (ref "R29") (pin "2") (pinfunction "2_2") (pintype "passive"))
      (node (ref "STM32F303VET6") (pin "79") (pinfunction "PC11_79") (pintype "bidirectional"))
    )
    (net (code "54") (name "EXT_TERM1") (class "Default")
      (node (ref "C1") (pin "1") (pinfunction "1_1") (pintype "passive"))
      (node (ref "D17") (pin "K") (pinfunction "C_K") (pintype "passive"))
      (node (ref "STM32F303VET6") (pin "63") (pinfunction "PC6_63") (pintype "bidirectional"))
      (node (ref "TERM1") (pin "P$2") (pinfunction "P$2_P$2") (pintype "bidirectional"))
    )
    (net (code "55") (name "EXT_TERM2") (class "Default")
      (node (ref "C19") (pin "1") (pinfunction "1_1") (pintype "passive"))
      (node (ref "D18") (pin "K") (pinfunction "C_K") (pintype "passive"))
      (node (ref "STM32F303VET6") (pin "64") (pinfunction "PC7_64") (pintype "bidirectional"))
      (node (ref "TERM1") (pin "P$3") (pinfunction "P$3_P$3") (pintype "bidirectional"))
    )
    (net (code "56") (name "EXT_TERM3") (class "Default")
      (node (ref "C22") (pin "1") (pinfunction "1_1") (pintype "passive"))
      (node (ref "D26") (pin "K") (pinfunction "C_K") (pintype "passive"))
      (node (ref "STM32F303VET6") (pin "87") (pinfunction "PD6_87") (pintype "bidirectional"))
      (node (ref "TERM2") (pin "P$4") (pinfunction "P$4_P$4") (pintype "bidirectional"))
    )
    (net (code "57") (name "GND") (class "Default")
      (node (ref "BOOT_ESP") (pin "1") (pinfunction "1_1") (pintype "passive"))
      (node (ref "C1") (pin "2") (pinfunction "2_2") (pintype "passive"))
      (node (ref "C10") (pin "2") (pinfunction "2_2") (pintype "passive"))
      (node (ref "C11") (pin "2") (pinfunction "2_2") (pintype "passive"))
      (node (ref "C12") (pin "1") (pinfunction "1_1") (pintype "passive"))
      (node (ref "C13") (pin "2") (pinfunction "2_2") (pintype "passive"))
      (node (ref "C14") (pin "2") (pinfunction "2_2") (pintype "passive"))
      (node (ref "C15") (pin "1") (pinfunction "1_1") (pintype "passive"))
      (node (ref "C17") (pin "2") (pinfunction "2_2") (pintype "passive"))
      (node (ref "C18") (pin "2") (pinfunction "2_2") (pintype "passive"))
      (node (ref "C19") (pin "2") (pinfunction "2_2") (pintype "passive"))
      (node (ref "C2") (pin "2") (pinfunction "2_2") (pintype "passive"))
      (node (ref "C21") (pin "2") (pinfunction "2_2") (pintype "passive"))
      (node (ref "C22") (pin "2") (pinfunction "2_2") (pintype "passive"))
      (node (ref "C23") (pin "2") (pinfunction "2_2") (pintype "passive"))
      (node (ref "C24") (pin "2") (pinfunction "2_2") (pintype "passive"))
      (node (ref "C25") (pin "2") (pinfunction "2_2") (pintype "passive"))
      (node (ref "C26") (pin "2") (pinfunction "2_2") (pintype "passive"))
      (node (ref "C27") (pin "2") (pinfunction "2_2") (pintype "passive"))
      (node (ref "C28") (pin "2") (pinfunction "2_2") (pintype "passive"))
      (node (ref "C29") (pin "2") (pinfunction "2_2") (pintype "passive"))
      (node (ref "C3") (pin "2") (pinfunction "2_2") (pintype "passive"))
      (node (ref "C30") (pin "2") (pinfunction "2_2") (pintype "passive"))
      (node (ref "C31") (pin "2") (pinfunction "2_2") (pintype "passive"))
      (node (ref "C32") (pin "2") (pinfunction "2_2") (pintype "passive"))
      (node (ref "C33") (pin "2") (pinfunction "2_2") (pintype "passive"))
      (node (ref "C4") (pin "1") (pinfunction "1_1") (pintype "passive"))
      (node (ref "C40") (pin "2") (pinfunction "2_2") (pintype "passive"))
      (node (ref "C41") (pin "2") (pinfunction "2_2") (pintype "passive"))
      (node (ref "C42") (pin "2") (pinfunction "2_2") (pintype "passive"))
      (node (ref "C45") (pin "2") (pinfunction "2_2") (pintype "passive"))
      (node (ref "C46") (pin "2") (pinfunction "2_2") (pintype "passive"))
      (node (ref "C47") (pin "2") (pinfunction "2_2") (pintype "passive"))
      (node (ref "C5") (pin "1") (pinfunction "1_1") (pintype "passive"))
      (node (ref "C50*") (pin "1") (pinfunction "1_1") (pintype "passive"))
      (node (ref "C6") (pin "1") (pinfunction "1_1") (pintype "passive"))
      (node (ref "C7") (pin "2") (pinfunction "2_2") (pintype "passive"))
      (node (ref "C8") (pin "1") (pinfunction "1_1") (pintype "passive"))
      (node (ref "C9") (pin "1") (pinfunction "1_1") (pintype "passive"))
      (node (ref "CF1") (pin "1") (pinfunction "1_1") (pintype "passive"))
      (node (ref "CF2") (pin "1") (pinfunction "1_1") (pintype "passive"))
      (node (ref "CF3") (pin "1") (pinfunction "1_1") (pintype "passive"))
      (node (ref "CF4") (pin "1") (pinfunction "1_1") (pintype "passive"))
      (node (ref "CF5") (pin "1") (pinfunction "1_1") (pintype "passive"))
      (node (ref "CF6") (pin "1") (pinfunction "1_1") (pintype "passive"))
      (node (ref "CF7") (pin "1") (pinfunction "1_1") (pintype "passive"))
      (node (ref "CF8") (pin "1") (pinfunction "1_1") (pintype "passive"))
      (node (ref "CF9") (pin "1") (pinfunction "1_1") (pintype "passive"))
      (node (ref "CV1") (pin "2") (pinfunction "2_2") (pintype "passive"))
      (node (ref "CV2") (pin "2") (pinfunction "2_2") (pintype "passive"))
      (node (ref "CV3") (pin "2") (pinfunction "2_2") (pintype "passive"))
      (node (ref "D10") (pin "A") (pinfunction "A_A") (pintype "passive"))
      (node (ref "D11") (pin "A") (pinfunction "A_A") (pintype "passive"))
      (node (ref "D12") (pin "A") (pinfunction "A_A") (pintype "passive"))
      (node (ref "D13") (pin "A") (pinfunction "A_A") (pintype "passive"))
      (node (ref "D14") (pin "A") (pinfunction "A_A") (pintype "passive"))
      (node (ref "D17") (pin "A") (pinfunction "A_A") (pintype "passive"))
      (node (ref "D18") (pin "A") (pinfunction "A_A") (pintype "passive"))
      (node (ref "D2") (pin "A") (pinfunction "A_A") (pintype "passive"))
      (node (ref "D22") (pin "A") (pinfunction "A_A") (pintype "passive"))
      (node (ref "D23") (pin "A") (pinfunction "A_A") (pintype "passive"))
      (node (ref "D26") (pin "A") (pinfunction "A_A") (pintype "passive"))
      (node (ref "D3") (pin "A") (pinfunction "A_A") (pintype "passive"))
      (node (ref "D33") (pin "A") (pinfunction "A_A") (pintype "passive"))
      (node (ref "D35") (pin "A") (pinfunction "A_A") (pintype "passive"))
      (node (ref "D4") (pin "A") (pinfunction "A_A") (pintype "passive"))
      (node (ref "D40*1") (pin "A") (pinfunction "A_A") (pintype "passive"))
      (node (ref "D5") (pin "A") (pinfunction "A_A") (pintype "passive"))
      (node (ref "D6") (pin "A") (pinfunction "A_A") (pintype "passive"))
      (node (ref "D7") (pin "A") (pinfunction "A_A") (pintype "passive"))
      (node (ref "D8") (pin "A") (pinfunction "A_A") (pintype "passive"))
      (node (ref "D9") (pin "A") (pinfunction "A_A") (pintype "passive"))
      (node (ref "EXPANSION") (pin "1") (pinfunction "1_1") (pintype "passive"))
      (node (ref "EXPANSION") (pin "14") (pinfunction "14_14") (pintype "passive"))
      (node (ref "EXPANSION") (pin "2") (pinfunction "2_2") (pintype "passive"))
      (node (ref "EXPANSION") (pin "25") (pinfunction "25_25") (pintype "passive"))
      (node (ref "EXPANSION") (pin "9") (pinfunction "9_9") (pintype "passive"))
      (node (ref "G1") (pin "-") (pinfunction "-_-") (pintype "passive"))
      (node (ref "J$1") (pin "GND@0") (pinfunction "GND_GND@0") (pintype "bidirectional"))
      (node (ref "J$1") (pin "GND@1") (pinfunction "GND_GND@1") (pintype "bidirectional"))
      (node (ref "J$1") (pin "GND@2") (pinfunction "GND_GND@2") (pintype "bidirectional"))
      (node (ref "J$1") (pin "GND@3") (pinfunction "GND_GND@3") (pintype "bidirectional"))
      (node (ref "LED1") (pin "C") (pinfunction "C_C") (pintype "passive"))
      (node (ref "LED2") (pin "C") (pinfunction "C_C") (pintype "passive"))
      (node (ref "LED3") (pin "C") (pinfunction "C_C") (pintype "passive"))
      (node (ref "LED4") (pin "C") (pinfunction "C_C") (pintype "passive"))
      (node (ref "MCP1825") (pin "2") (pinfunction "GND_2") (pintype "power_in"))
      (node (ref "MCP1825") (pin "4") (pinfunction "GND_4") (pintype "power_in"))
      (node (ref "OLED") (pin "4") (pinfunction "4_4") (pintype "passive"))
      (node (ref "PCB2") (pin "P$46") (pinfunction "GND_P$46") (pintype "bidirectional"))
      (node (ref "PCB2") (pin "P$49") (pinfunction "GND_P$49") (pintype "bidirectional"))
      (node (ref "PCB2") (pin "P$54") (pinfunction "GND_P$54") (pintype "bidirectional"))
      (node (ref "PCB2") (pin "P$60") (pinfunction "GND_P$60") (pintype "bidirectional"))
      (node (ref "PCB2") (pin "P$65") (pinfunction "GND_P$65") (pintype "bidirectional"))
      (node (ref "PCB2") (pin "P$70") (pinfunction "GND_P$70") (pintype "bidirectional"))
      (node (ref "PCB2") (pin "P$74") (pinfunction "GND_P$74") (pintype "bidirectional"))
      (node (ref "PCB2") (pin "P$79") (pinfunction "GND_P$79") (pintype "bidirectional"))
      (node (ref "PS1") (pin "4") (pinfunction "GND_4") (pintype "power_in"))
      (node (ref "Q2") (pin "2") (pinfunction "E_2") (pintype "passive"))
      (node (ref "Q3") (pin "2") (pinfunction "E_2") (pintype "passive"))
      (node (ref "Q4") (pin "1") (pinfunction "G_1") (pintype "passive"))
      (node (ref "R14") (pin "1") (pinfunction "1_1") (pintype "passive"))
      (node (ref "R15") (pin "1") (pinfunction "1_1") (pintype "passive"))
      (node (ref "R16") (pin "1") (pinfunction "1_1") (pintype "passive"))
      (node (ref "R2") (pin "2") (pinfunction "2_2") (pintype "passive"))
      (node (ref "R23") (pin "1") (pinfunction "1_1") (pintype "passive"))
      (node (ref "RFM69HCW") (pin "10") (pinfunction "GND_10") (pintype "passive"))
      (node (ref "RFM69HCW") (pin "7") (pinfunction "GND_7") (pintype "passive"))
      (node (ref "RJ1") (pin "1") (pinfunction "1_1") (pintype "bidirectional"))
      (node (ref "RJ1") (pin "3") (pinfunction "3_3") (pintype "bidirectional"))
      (node (ref "RJ1") (pin "5") (pinfunction "5_5") (pintype "bidirectional"))
      (node (ref "RJ2") (pin "1") (pinfunction "1_1") (pintype "bidirectional"))
      (node (ref "RJ2") (pin "3") (pinfunction "3_3") (pintype "bidirectional"))
      (node (ref "RJ2") (pin "5") (pinfunction "5_5") (pintype "bidirectional"))
      (node (ref "S1") (pin "1") (pinfunction "P_1") (pintype "passive"))
      (node (ref "S2") (pin "1") (pinfunction "1_1") (pintype "bidirectional"))
      (node (ref "STM32F303VET6") (pin "20") (pinfunction "VSSA/VREF-_20") (pintype "bidirectional"))
      (node (ref "STM32F303VET6") (pin "49") (pinfunction "VSS_49") (pintype "bidirectional"))
      (node (ref "STM32F303VET6") (pin "74") (pinfunction "VSS_74") (pintype "bidirectional"))
      (node (ref "STM32F303VET6") (pin "99") (pinfunction "VSS_99") (pintype "bidirectional"))
      (node (ref "SV1") (pin "1") (pinfunction "1_1") (pintype "passive"))
      (node (ref "SV2") (pin "1") (pinfunction "1_1") (pintype "passive"))
      (node (ref "TERM1") (pin "P$6") (pinfunction "P$6_P$6") (pintype "bidirectional"))
      (node (ref "TERM2") (pin "P$3") (pinfunction "P$3_P$3") (pintype "bidirectional"))
      (node (ref "TERM3") (pin "P$6") (pinfunction "P$6_P$6") (pintype "bidirectional"))
      (node (ref "U$2") (pin "P$1") (pinfunction "GND_P$1") (pintype "bidirectional"))
      (node (ref "U$2") (pin "P$2") (pinfunction "GND._P$2") (pintype "bidirectional"))
      (node (ref "U$7") (pin "P$1") (pinfunction "GND_P$1") (pintype "bidirectional"))
      (node (ref "U$7") (pin "P$2") (pinfunction "GND_P$2") (pintype "bidirectional"))
      (node (ref "U$7") (pin "P$3") (pinfunction "GND_P$3") (pintype "bidirectional"))
      (node (ref "U$7") (pin "P$4") (pinfunction "GND_P$4") (pintype "bidirectional"))
      (node (ref "U$7") (pin "PIN6") (pinfunction "VSS_PIN6") (pintype "bidirectional"))
      (node (ref "U1") (pin "1") (pinfunction "GND_1") (pintype "power_in"))
      (node (ref "U1") (pin "15") (pinfunction "GND_15") (pintype "power_in"))
      (node (ref "U1") (pin "31") (pinfunction "IO19_31") (pintype "bidirectional"))
      (node (ref "U1") (pin "38") (pinfunction "GND_38") (pintype "power_in"))
      (node (ref "U1") (pin "39") (pinfunction "GND_39") (pintype "power_in"))
      (node (ref "UART_STM") (pin "1") (pinfunction "1_1") (pintype "passive"))
      (node (ref "USB-C") (pin "A1/B12") (pinfunction "GND1_A1/B12") (pintype "passive"))
      (node (ref "USB-C") (pin "B1/A12") (pinfunction "GND2_B1/A12") (pintype "passive"))
      (node (ref "USB-C") (pin "GND1") (pinfunction "SHIELD_GND1") (pintype "bidirectional"))
      (node (ref "USB-C") (pin "GND2") (pinfunction "SHIELD_GND2") (pintype "bidirectional"))
      (node (ref "USB-C") (pin "GND3") (pinfunction "SHIELD_GND3") (pintype "bidirectional"))
      (node (ref "USB-C") (pin "GND4") (pinfunction "SHIELD_GND4") (pintype "bidirectional"))
    )
    (net (code "58") (name "HSE_IN") (class "Default")
      (node (ref "C30") (pin "1") (pinfunction "1_1") (pintype "passive"))
      (node (ref "HSE") (pin "1") (pinfunction "1_1") (pintype "passive"))
      (node (ref "STM32F303VET6") (pin "12") (pinfunction "PF0/OSC_IN_12") (pintype "bidirectional"))
    )
    (net (code "59") (name "HSE_OUT") (class "Default")
      (node (ref "R21") (pin "1") (pinfunction "1_1") (pintype "passive"))
      (node (ref "STM32F303VET6") (pin "13") (pinfunction "PF1/OSC_OUT_13") (pintype "bidirectional"))
    )
    (net (code "60") (name "HSPI_CLK") (class "Default")
      (node (ref "JP8") (pin "3") (pinfunction "3_3") (pintype "passive"))
      (node (ref "SJ10") (pin "1") (pinfunction "1_1") (pintype "passive"))
      (node (ref "U1") (pin "13") (pinfunction "IO14_13") (pintype "bidirectional"))
    )
    (net (code "61") (name "HSPI_CS0") (class "Default")
      (node (ref "JP2") (pin "3") (pinfunction "3_3") (pintype "passive"))
      (node (ref "SJ13") (pin "1") (pinfunction "1_1") (pintype "passive"))
      (node (ref "U1") (pin "23") (pinfunction "IO15_23") (pintype "bidirectional"))
    )
    (net (code "62") (name "HSPI_ID{slash}MOSI") (class "Default")
      (node (ref "JP3") (pin "3") (pinfunction "3_3") (pintype "passive"))
      (node (ref "SJ9") (pin "1") (pinfunction "1_1") (pintype "passive"))
      (node (ref "U1") (pin "16") (pinfunction "IO13_16") (pintype "bidirectional"))
    )
    (net (code "63") (name "HSPI_Q{slash}MISO") (class "Default")
      (node (ref "JP7") (pin "3") (pinfunction "3_3") (pintype "passive"))
      (node (ref "SJ4") (pin "1") (pinfunction "1_1") (pintype "passive"))
      (node (ref "U1") (pin "14") (pinfunction "IO12_14") (pintype "bidirectional"))
    )
    (net (code "64") (name "LED1_GREEN") (class "Default")
      (node (ref "R3") (pin "2") (pinfunction "2_2") (pintype "passive"))
      (node (ref "STM32F303VET6") (pin "55") (pinfunction "PD8_55") (pintype "bidirectional"))
    )
    (net (code "65") (name "LED2_YELLOW") (class "Default")
      (node (ref "R4") (pin "2") (pinfunction "2_2") (pintype "passive"))
      (node (ref "STM32F303VET6") (pin "56") (pinfunction "PD9_56") (pintype "bidirectional"))
    )
    (net (code "66") (name "LED3_RED") (class "Default")
      (node (ref "R5") (pin "2") (pinfunction "2_2") (pintype "passive"))
      (node (ref "STM32F303VET6") (pin "57") (pinfunction "PD10_57") (pintype "bidirectional"))
    )
    (net (code "67") (name "MOS1") (class "Default")
      (node (ref "Q11_") (pin "1") (pinfunction "G_1") (pintype "bidirectional"))
      (node (ref "STM32F303VET6") (pin "38") (pinfunction "PE7_38") (pintype "bidirectional"))
      (node (ref "TP17") (pin "1") (pinfunction "1_1") (pintype "bidirectional"))
    )
    (net (code "68") (name "MOS2") (class "Default")
      (node (ref "Q12_") (pin "1") (pinfunction "G_1") (pintype "bidirectional"))
      (node (ref "STM32F303VET6") (pin "39") (pinfunction "PE8_39") (pintype "bidirectional"))
    )
    (net (code "69") (name "MOS3") (class "Default")
      (node (ref "Q13_") (pin "1") (pinfunction "G_1") (pintype "bidirectional"))
      (node (ref "STM32F303VET6") (pin "40") (pinfunction "PE9_40") (pintype "bidirectional"))
    )
    (net (code "70") (name "MOS4") (class "Default")
      (node (ref "Q14_") (pin "1") (pinfunction "G_1") (pintype "bidirectional"))
      (node (ref "STM32F303VET6") (pin "41") (pinfunction "PE10_41") (pintype "bidirectional"))
    )
    (net (code "71") (name "MOS5") (class "Default")
      (node (ref "Q15_") (pin "1") (pinfunction "G_1") (pintype "bidirectional"))
      (node (ref "STM32F303VET6") (pin "42") (pinfunction "PE11_42") (pintype "bidirectional"))
    )
    (net (code "72") (name "MOS6") (class "Default")
      (node (ref "Q16_") (pin "1") (pinfunction "G_1") (pintype "bidirectional"))
      (node (ref "STM32F303VET6") (pin "43") (pinfunction "PE12_43") (pintype "bidirectional"))
    )
    (net (code "73") (name "MOS7") (class "Default")
      (node (ref "Q17_") (pin "1") (pinfunction "G_1") (pintype "bidirectional"))
      (node (ref "STM32F303VET6") (pin "44") (pinfunction "PE13_44") (pintype "bidirectional"))
    )
    (net (code "74") (name "MOS8") (class "Default")
      (node (ref "Q18_") (pin "1") (pinfunction "G_1") (pintype "bidirectional"))
      (node (ref "STM32F303VET6") (pin "45") (pinfunction "PE14_45") (pintype "bidirectional"))
    )
    (net (code "75") (name "MOS9") (class "Default")
      (node (ref "Q19_") (pin "1") (pinfunction "G_1") (pintype "bidirectional"))
      (node (ref "STM32F303VET6") (pin "46") (pinfunction "PE15_46") (pintype "bidirectional"))
    )
    (net (code "76") (name "NRST_STM") (class "Default")
      (node (ref "S2") (pin "2") (pinfunction "2_2") (pintype "bidirectional"))
      (node (ref "SJ25") (pin "2") (pinfunction "2_2") (pintype "passive"))
      (node (ref "SJ32") (pin "1") (pinfunction "1_1") (pintype "passive"))
      (node (ref "STM32F303VET6") (pin "14") (pinfunction "NRST_14") (pintype "bidirectional"))
      (node (ref "ST_LINK") (pin "3") (pinfunction "3_3") (pintype "passive"))
      (node (ref "SV1") (pin "6") (pinfunction "6_6") (pintype "passive"))
      (node (ref "UART_STM") (pin "6") (pinfunction "6_6") (pintype "passive"))
    )
    (net (code "77") (name "Net-(C16-Pad1)") (class "Default")
      (node (ref "C16") (pin "1") (pinfunction "1_1") (pintype "passive"))
      (node (ref "SV2") (pin "6") (pinfunction "6_6") (pintype "passive"))
    )
    (net (code "78") (name "Net-(CT1-2)") (class "Default")
      (node (ref "CT1") (pin "P$2") (pinfunction "2_P$2") (pintype "bidirectional"))
      (node (ref "D13") (pin "K") (pinfunction "C_K") (pintype "passive"))
      (node (ref "D29") (pin "A") (pinfunction "A_A") (pintype "passive"))
      (node (ref "Q11_") (pin "2") (pinfunction "S_2") (pintype "bidirectional"))
      (node (ref "RB1") (pin "1") (pinfunction "1_1") (pintype "passive"))
      (node (ref "RB1_") (pin "1") (pinfunction "1_1") (pintype "passive"))
      (node (ref "RF1") (pin "1") (pinfunction "1_1") (pintype "passive"))
    )
    (net (code "79") (name "Net-(CT1-4)") (class "Default")
      (node (ref "CT1") (pin "P$4") (pinfunction "4_P$4") (pintype "bidirectional"))
      (node (ref "JP4") (pin "1") (pinfunction "1_1") (pintype "passive"))
      (node (ref "RB1") (pin "2") (pinfunction "2_2") (pintype "passive"))
      (node (ref "RB1Q") (pin "1") (pinfunction "1_1") (pintype "passive"))
      (node (ref "RB1_") (pin "2") (pinfunction "2_2") (pintype "passive"))
    )
    (net (code "80") (name "Net-(CT2-2)") (class "Default")
      (node (ref "CT2") (pin "P$2") (pinfunction "2_P$2") (pintype "bidirectional"))
      (node (ref "D12") (pin "K") (pinfunction "C_K") (pintype "passive"))
      (node (ref "D28") (pin "A") (pinfunction "A_A") (pintype "passive"))
      (node (ref "Q12_") (pin "2") (pinfunction "S_2") (pintype "bidirectional"))
      (node (ref "RB2") (pin "1") (pinfunction "1_1") (pintype "passive"))
      (node (ref "RB2_") (pin "1") (pinfunction "1_1") (pintype "passive"))
      (node (ref "RF2") (pin "1") (pinfunction "1_1") (pintype "passive"))
    )
    (net (code "81") (name "Net-(CT2-4)") (class "Default")
      (node (ref "CT2") (pin "P$4") (pinfunction "4_P$4") (pintype "bidirectional"))
      (node (ref "JP5") (pin "1") (pinfunction "1_1") (pintype "passive"))
      (node (ref "RB2") (pin "2") (pinfunction "2_2") (pintype "passive"))
      (node (ref "RB2Q") (pin "1") (pinfunction "1_1") (pintype "passive"))
      (node (ref "RB2_") (pin "2") (pinfunction "2_2") (pintype "passive"))
    )
    (net (code "82") (name "Net-(CT3-2)") (class "Default")
      (node (ref "CT3") (pin "P$2") (pinfunction "2_P$2") (pintype "bidirectional"))
      (node (ref "D11") (pin "K") (pinfunction "C_K") (pintype "passive"))
      (node (ref "D27") (pin "A") (pinfunction "A_A") (pintype "passive"))
      (node (ref "Q13_") (pin "2") (pinfunction "S_2") (pintype "bidirectional"))
      (node (ref "RB3") (pin "1") (pinfunction "1_1") (pintype "passive"))
      (node (ref "RB3_") (pin "1") (pinfunction "1_1") (pintype "passive"))
      (node (ref "RF3") (pin "1") (pinfunction "1_1") (pintype "passive"))
    )
    (net (code "83") (name "Net-(CT3-4)") (class "Default")
      (node (ref "CT3") (pin "P$4") (pinfunction "4_P$4") (pintype "bidirectional"))
      (node (ref "JP6") (pin "1") (pinfunction "1_1") (pintype "passive"))
      (node (ref "RB3") (pin "2") (pinfunction "2_2") (pintype "passive"))
      (node (ref "RB3Q") (pin "1") (pinfunction "1_1") (pintype "passive"))
      (node (ref "RB3_") (pin "2") (pinfunction "2_2") (pintype "passive"))
    )
    (net (code "84") (name "Net-(CT4-2)") (class "Default")
      (node (ref "CT4") (pin "P$2") (pinfunction "2_P$2") (pintype "bidirectional"))
      (node (ref "D10") (pin "K") (pinfunction "C_K") (pintype "passive"))
      (node (ref "D25") (pin "A") (pinfunction "A_A") (pintype "passive"))
      (node (ref "Q14_") (pin "2") (pinfunction "S_2") (pintype "bidirectional"))
      (node (ref "RB4") (pin "1") (pinfunction "1_1") (pintype "passive"))
      (node (ref "RB4_") (pin "1") (pinfunction "1_1") (pintype "passive"))
      (node (ref "RF4") (pin "1") (pinfunction "1_1") (pintype "passive"))
    )
    (net (code "85") (name "Net-(CT5-2)") (class "Default")
      (node (ref "CT5") (pin "P$2") (pinfunction "2_P$2") (pintype "bidirectional"))
      (node (ref "D20") (pin "A") (pinfunction "A_A") (pintype "passive"))
      (node (ref "D9") (pin "K") (pinfunction "C_K") (pintype "passive"))
      (node (ref "Q15_") (pin "2") (pinfunction "S_2") (pintype "bidirectional"))
      (node (ref "RB5") (pin "1") (pinfunction "1_1") (pintype "passive"))
      (node (ref "RB5_") (pin "1") (pinfunction "1_1") (pintype "passive"))
      (node (ref "RF5") (pin "1") (pinfunction "1_1") (pintype "passive"))
    )
    (net (code "86") (name "Net-(CT6-2)") (class "Default")
      (node (ref "CT6") (pin "P$2") (pinfunction "2_P$2") (pintype "bidirectional"))
      (node (ref "D24") (pin "A") (pinfunction "A_A") (pintype "passive"))
      (node (ref "D8") (pin "K") (pinfunction "C_K") (pintype "passive"))
      (node (ref "Q16_") (pin "2") (pinfunction "S_2") (pintype "bidirectional"))
      (node (ref "RB6") (pin "1") (pinfunction "1_1") (pintype "passive"))
      (node (ref "RB6_") (pin "1") (pinfunction "1_1") (pintype "passive"))
      (node (ref "RF6") (pin "1") (pinfunction "1_1") (pintype "passive"))
    )
    (net (code "87") (name "Net-(CT7-2)") (class "Default")
      (node (ref "CT7") (pin "P$2") (pinfunction "2_P$2") (pintype "bidirectional"))
      (node (ref "D19") (pin "A") (pinfunction "A_A") (pintype "passive"))
      (node (ref "D7") (pin "K") (pinfunction "C_K") (pintype "passive"))
      (node (ref "Q17_") (pin "2") (pinfunction "S_2") (pintype "bidirectional"))
      (node (ref "RB7") (pin "1") (pinfunction "1_1") (pintype "passive"))
      (node (ref "RB7_") (pin "1") (pinfunction "1_1") (pintype "passive"))
      (node (ref "RF7") (pin "1") (pinfunction "1_1") (pintype "passive"))
    )
    (net (code "88") (name "Net-(CT8-2)") (class "Default")
      (node (ref "CT8") (pin "P$2") (pinfunction "2_P$2") (pintype "bidirectional"))
      (node (ref "D16") (pin "A") (pinfunction "A_A") (pintype "passive"))
      (node (ref "D6") (pin "K") (pinfunction "C_K") (pintype "passive"))
      (node (ref "Q18_") (pin "2") (pinfunction "S_2") (pintype "bidirectional"))
      (node (ref "RB8") (pin "1") (pinfunction "1_1") (pintype "passive"))
      (node (ref "RB8_") (pin "1") (pinfunction "1_1") (pintype "passive"))
      (node (ref "RF8") (pin "1") (pinfunction "1_1") (pintype "passive"))
    )
    (net (code "89") (name "Net-(CT9-2)") (class "Default")
      (node (ref "CT9") (pin "P$2") (pinfunction "2_P$2") (pintype "bidirectional"))
      (node (ref "D15") (pin "A") (pinfunction "A_A") (pintype "passive"))
      (node (ref "D5") (pin "K") (pinfunction "C_K") (pintype "passive"))
      (node (ref "Q19_") (pin "2") (pinfunction "S_2") (pintype "bidirectional"))
      (node (ref "RB9") (pin "1") (pinfunction "1_1") (pintype "passive"))
      (node (ref "RB9_") (pin "1") (pinfunction "1_1") (pintype "passive"))
      (node (ref "RF9") (pin "1") (pinfunction "1_1") (pintype "passive"))
    )
    (net (code "90") (name "Net-(FB1-P$1)") (class "Default")
      (node (ref "FB1") (pin "1") (pinfunction "P$1_1") (pintype "passive"))
      (node (ref "USB-C") (pin "A4/B9") (pinfunction "VBUS1_A4/B9") (pintype "passive"))
      (node (ref "USB-C") (pin "B4/A9") (pinfunction "VBUS2_B4/A9") (pintype "passive"))
    )
    (net (code "91") (name "Net-(HSE-2)") (class "Default")
      (node (ref "C29") (pin "1") (pinfunction "1_1") (pintype "passive"))
      (node (ref "HSE") (pin "3") (pinfunction "2_3") (pintype "passive"))
      (node (ref "R21") (pin "2") (pinfunction "2_2") (pintype "passive"))
    )
    (net (code "92") (name "Net-(J$1-SIGNAL)") (class "Default")
      (node (ref "J$1") (pin "SIG") (pinfunction "SIGNAL_SIG") (pintype "bidirectional"))
      (node (ref "RFM69HCW") (pin "8") (pinfunction "ANT_8") (pintype "bidirectional"))
    )
    (net (code "93") (name "Net-(JP1-Pad2)") (class "Default")
      (node (ref "JP1") (pin "2") (pinfunction "2_2") (pintype "passive"))
      (node (ref "R22") (pin "2") (pinfunction "2_2") (pintype "passive"))
    )
    (net (code "94") (name "Net-(LED1-PadA)") (class "Default")
      (node (ref "LED1") (pin "A") (pinfunction "A_A") (pintype "passive"))
      (node (ref "R3") (pin "1") (pinfunction "1_1") (pintype "passive"))
    )
    (net (code "95") (name "Net-(LED2-PadA)") (class "Default")
      (node (ref "LED2") (pin "A") (pinfunction "A_A") (pintype "passive"))
      (node (ref "R4") (pin "1") (pinfunction "1_1") (pintype "passive"))
    )
    (net (code "96") (name "Net-(LED3-PadA)") (class "Default")
      (node (ref "LED3") (pin "A") (pinfunction "A_A") (pintype "passive"))
      (node (ref "R5") (pin "1") (pinfunction "1_1") (pintype "passive"))
    )
    (net (code "97") (name "Net-(LED4-PadA)") (class "Default")
      (node (ref "LED4") (pin "A") (pinfunction "A_A") (pintype "passive"))
      (node (ref "R10") (pin "1") (pinfunction "1_1") (pintype "passive"))
    )
    (net (code "98") (name "Net-(PCB2-3V3-PadP$57)") (class "Default")
      (node (ref "PCB2") (pin "P$57") (pinfunction "3V3_P$57") (pintype "bidirectional"))
      (node (ref "R28") (pin "2") (pinfunction "2_2") (pintype "passive"))
    )
    (net (code "99") (name "Net-(PCB2-GPIO2)") (class "Default")
      (node (ref "PCB2") (pin "P$43") (pinfunction "GPIO2_P$43") (pintype "bidirectional"))
      (node (ref "SJ26") (pin "2") (pinfunction "2_2") (pintype "passive"))
    )
    (net (code "100") (name "Net-(PCB2-GPIO3)") (class "Default")
      (node (ref "PCB2") (pin "P$45") (pinfunction "GPIO3_P$45") (pintype "bidirectional"))
      (node (ref "SJ27") (pin "1") (pinfunction "1_1") (pintype "passive"))
    )
    (net (code "101") (name "Net-(PCB2-GPIO4)") (class "Default")
      (node (ref "J1") (pin "2") (pinfunction "2_2") (pintype "passive"))
      (node (ref "PCB2") (pin "P$47") (pinfunction "GPIO4_P$47") (pintype "bidirectional"))
    )
    (net (code "102") (name "Net-(PCB2-GPIO8)") (class "Default")
      (node (ref "PCB2") (pin "P$64") (pinfunction "GPIO8_P$64") (pintype "bidirectional"))
      (node (ref "SJ14") (pin "1") (pinfunction "1_1") (pintype "passive"))
    )
    (net (code "103") (name "Net-(PCB2-GPIO16)") (class "Default")
      (node (ref "PCB2") (pin "P$76") (pinfunction "GPIO16_P$76") (pintype "bidirectional"))
      (node (ref "R12") (pin "1") (pinfunction "1_1") (pintype "passive"))
    )
    (net (code "104") (name "Net-(PCB2-GPIO17)") (class "Default")
      (node (ref "PCB2") (pin "P$51") (pinfunction "GPIO17_P$51") (pintype "bidirectional"))
      (node (ref "SJ32") (pin "2") (pinfunction "2_2") (pintype "passive"))
    )
    (net (code "105") (name "Net-(PCB2-GPIO20)") (class "Default")
      (node (ref "PCB2") (pin "P$78") (pinfunction "GPIO20_P$78") (pintype "bidirectional"))
      (node (ref "R24") (pin "1") (pinfunction "1_1") (pintype "passive"))
    )
    (net (code "106") (name "Net-(Q1-B)") (class "Default")
      (node (ref "Q1") (pin "1") (pinfunction "B_1") (pintype "passive"))
      (node (ref "Q3") (pin "3") (pinfunction "C_3") (pintype "passive"))
      (node (ref "R14") (pin "2") (pinfunction "2_2") (pintype "passive"))
      (node (ref "R9") (pin "1") (pinfunction "1_1") (pintype "passive"))
    )
    (net (code "107") (name "Net-(Q1-C)") (class "Default")
      (node (ref "Q1") (pin "3") (pinfunction "C_3") (pintype "passive"))
      (node (ref "Q2") (pin "1") (pinfunction "B_1") (pintype "passive"))
      (node (ref "R16") (pin "2") (pinfunction "2_2") (pintype "passive"))
    )
    (net (code "108") (name "Net-(Q2-C)") (class "Default")
      (node (ref "Q2") (pin "3") (pinfunction "C_3") (pintype "passive"))
      (node (ref "R11") (pin "1") (pinfunction "1_1") (pintype "passive"))
      (node (ref "R15") (pin "2") (pinfunction "2_2") (pintype "passive"))
      (node (ref "R19") (pin "1") (pinfunction "1_1") (pintype "passive"))
    )
    (net (code "109") (name "Net-(Q3-B)") (class "Default")
      (node (ref "Q3") (pin "1") (pinfunction "B_1") (pintype "passive"))
      (node (ref "R18") (pin "1") (pinfunction "1_1") (pintype "passive"))
    )
    (net (code "110") (name "Net-(Q4-S)") (class "Default")
      (node (ref "Q4") (pin "2") (pinfunction "S_2") (pintype "passive"))
      (node (ref "R8") (pin "1") (pinfunction "1_1") (pintype "passive"))
    )
    (net (code "111") (name "Net-(Q11_-D)") (class "Default")
      (node (ref "Q11_") (pin "3") (pinfunction "D_3") (pintype "bidirectional"))
      (node (ref "RB1Q") (pin "2") (pinfunction "2_2") (pintype "passive"))
    )
    (net (code "112") (name "Net-(Q12_-D)") (class "Default")
      (node (ref "Q12_") (pin "3") (pinfunction "D_3") (pintype "bidirectional"))
      (node (ref "RB2Q") (pin "2") (pinfunction "2_2") (pintype "passive"))
    )
    (net (code "113") (name "Net-(Q13_-D)") (class "Default")
      (node (ref "Q13_") (pin "3") (pinfunction "D_3") (pintype "bidirectional"))
      (node (ref "RB3Q") (pin "2") (pinfunction "2_2") (pintype "passive"))
    )
    (net (code "114") (name "Net-(Q14_-D)") (class "Default")
      (node (ref "Q14_") (pin "3") (pinfunction "D_3") (pintype "bidirectional"))
      (node (ref "RB4Q") (pin "2") (pinfunction "2_2") (pintype "passive"))
    )
    (net (code "115") (name "Net-(Q15_-D)") (class "Default")
      (node (ref "Q15_") (pin "3") (pinfunction "D_3") (pintype "bidirectional"))
      (node (ref "RB5Q") (pin "2") (pinfunction "2_2") (pintype "passive"))
    )
    (net (code "116") (name "Net-(Q16_-D)") (class "Default")
      (node (ref "Q16_") (pin "3") (pinfunction "D_3") (pintype "bidirectional"))
      (node (ref "RB6Q") (pin "2") (pinfunction "2_2") (pintype "passive"))
    )
    (net (code "117") (name "Net-(Q17_-D)") (class "Default")
      (node (ref "Q17_") (pin "3") (pinfunction "D_3") (pintype "bidirectional"))
      (node (ref "RB7Q") (pin "2") (pinfunction "2_2") (pintype "passive"))
    )
    (net (code "118") (name "Net-(Q18_-D)") (class "Default")
      (node (ref "Q18_") (pin "3") (pinfunction "D_3") (pintype "bidirectional"))
      (node (ref "RB8Q") (pin "2") (pinfunction "2_2") (pintype "passive"))
    )
    (net (code "119") (name "Net-(Q19_-D)") (class "Default")
      (node (ref "Q19_") (pin "3") (pinfunction "D_3") (pintype "bidirectional"))
      (node (ref "RB9Q") (pin "2") (pinfunction "2_2") (pintype "passive"))
    )
    (net (code "120") (name "Net-(SJ1-Pad1)") (class "Default")
      (node (ref "SJ1") (pin "1") (pinfunction "1_1") (pintype "passive"))
      (node (ref "SV1") (pin "2") (pinfunction "2_2") (pintype "passive"))
    )
    (net (code "121") (name "Net-(STM32F303VET6-PB14)") (class "Default")
      (node (ref "SJ3") (pin "2") (pinfunction "2_2") (pintype "passive"))
      (node (ref "STM32F303VET6") (pin "53") (pinfunction "PB14_53") (pintype "bidirectional"))
    )
    (net (code "122") (name "Net-(U1-3V3)") (class "Default")
      (node (ref "R29") (pin "1") (pinfunction "1_1") (pintype "passive"))
      (node (ref "SJ23") (pin "1") (pinfunction "1_1") (pintype "passive"))
      (node (ref "U1") (pin "2") (pinfunction "3V3_2") (pintype "power_in"))
    )
    (net (code "123") (name "Net-(U1-EN)") (class "Default")
      (node (ref "C16") (pin "2") (pinfunction "2_2") (pintype "passive"))
      (node (ref "U1") (pin "3") (pinfunction "EN_3") (pintype "input"))
    )
    (net (code "124") (name "Net-(U1-IO0)") (class "Default")
      (node (ref "BOOT_ESP") (pin "2") (pinfunction "2_2") (pintype "passive"))
      (node (ref "U1") (pin "25") (pinfunction "IO0_25") (pintype "bidirectional"))
    )
    (net (code "125") (name "Net-(U1-IO18)") (class "Default")
      (node (ref "SJ25") (pin "1") (pinfunction "1_1") (pintype "passive"))
      (node (ref "U1") (pin "30") (pinfunction "IO18_30") (pintype "bidirectional"))
    )
    (net (code "126") (name "PULSE1_RJ45") (class "Default")
      (node (ref "C41") (pin "1") (pinfunction "1_1") (pintype "passive"))
      (node (ref "RJ1") (pin "6") (pinfunction "6_6") (pintype "bidirectional"))
      (node (ref "STM32F303VET6") (pin "71") (pinfunction "PA12_71") (pintype "bidirectional"))
    )
    (net (code "127") (name "PULSE_2_RJ45") (class "Default")
      (node (ref "C46") (pin "1") (pinfunction "1_1") (pintype "passive"))
      (node (ref "RJ2") (pin "6") (pinfunction "6_6") (pintype "bidirectional"))
      (node (ref "STM32F303VET6") (pin "73") (pinfunction "PF6_73") (pintype "bidirectional"))
    )
    (net (code "128") (name "RPI_GPIO16") (class "Default")
      (node (ref "R12") (pin "2") (pinfunction "2_2") (pintype "passive"))
      (node (ref "STM32F303VET6") (pin "59") (pinfunction "PD12_59") (pintype "bidirectional"))
    )
    (net (code "129") (name "RPI_GPIO20") (class "Default")
      (node (ref "R24") (pin "2") (pinfunction "2_2") (pintype "passive"))
      (node (ref "STM32F303VET6") (pin "60") (pinfunction "PD13_60") (pintype "bidirectional"))
    )
    (net (code "130") (name "RPI_PWR") (class "Default")
      (node (ref "R28") (pin "1") (pinfunction "1_1") (pintype "passive"))
      (node (ref "STM32F303VET6") (pin "62") (pinfunction "PD15_62") (pintype "bidirectional"))
      (node (ref "TP11") (pin "P$1") (pinfunction "1_P$1") (pintype "bidirectional"))
    )
    (net (code "131") (name "RST_RFM") (class "Default")
      (node (ref "RFM69HCW") (pin "6") (pinfunction "~{RES}_6") (pintype "bidirectional"))
      (node (ref "STM32F303VET6") (pin "97") (pinfunction "PE0_97") (pintype "bidirectional"))
    )
    (net (code "132") (name "SCL") (class "Default")
      (node (ref "D34") (pin "A") (pinfunction "A_A") (pintype "passive"))
      (node (ref "D35") (pin "K") (pinfunction "C_K") (pintype "passive"))
      (node (ref "EXPANSION") (pin "22") (pinfunction "22_22") (pintype "passive"))
      (node (ref "OLED") (pin "2") (pinfunction "2_2") (pintype "passive"))
      (node (ref "R13") (pin "2") (pinfunction "2_2") (pintype "passive"))
      (node (ref "SJ27") (pin "2") (pinfunction "2_2") (pintype "passive"))
      (node (ref "STM32F303VET6") (pin "65") (pinfunction "PC8_65") (pintype "bidirectional"))
      (node (ref "TERM1") (pin "P$5") (pinfunction "P$5_P$5") (pintype "bidirectional"))
      (node (ref "U1") (pin "36") (pinfunction "IO22_36") (pintype "bidirectional"))
    )
    (net (code "133") (name "SDA") (class "Default")
      (node (ref "D21") (pin "A") (pinfunction "A_A") (pintype "passive"))
      (node (ref "D33") (pin "K") (pinfunction "C_K") (pintype "passive"))
      (node (ref "EXPANSION") (pin "20") (pinfunction "20_20") (pintype "passive"))
      (node (ref "OLED") (pin "1") (pinfunction "1_1") (pintype "passive"))
      (node (ref "R20") (pin "2") (pinfunction "2_2") (pintype "passive"))
      (node (ref "SJ26") (pin "1") (pinfunction "1_1") (pintype "passive"))
      (node (ref "STM32F303VET6") (pin "66") (pinfunction "PC9_66") (pintype "bidirectional"))
      (node (ref "TERM1") (pin "P$4") (pinfunction "P$4_P$4") (pintype "bidirectional"))
      (node (ref "U1") (pin "33") (pinfunction "IO21_33") (pintype "bidirectional"))
    )
    (net (code "134") (name "SPI1_CLK_SLAVE") (class "Default")
      (node (ref "SJ10") (pin "2") (pinfunction "2_2") (pintype "passive"))
      (node (ref "SJ7") (pin "1") (pinfunction "1_1") (pintype "passive"))
      (node (ref "STM32F303VET6") (pin "89") (pinfunction "PB3_89") (pintype "bidirectional"))
      (node (ref "TP1") (pin "P$1") (pinfunction "1_P$1") (pintype "bidirectional"))
    )
    (net (code "135") (name "SPI1_MISO_SLAVE") (class "Default")
      (node (ref "SJ4") (pin "2") (pinfunction "2_2") (pintype "passive"))
      (node (ref "SJ6") (pin "1") (pinfunction "1_1") (pintype "passive"))
      (node (ref "STM32F303VET6") (pin "90") (pinfunction "PB4_90") (pintype "bidirectional"))
      (node (ref "TP2") (pin "P$1") (pinfunction "1_P$1") (pintype "bidirectional"))
    )
    (net (code "136") (name "SPI1_MOSI_SLAVE") (class "Default")
      (node (ref "SJ5") (pin "1") (pinfunction "1_1") (pintype "passive"))
      (node (ref "SJ9") (pin "2") (pinfunction "2_2") (pintype "passive"))
      (node (ref "STM32F303VET6") (pin "91") (pinfunction "PB5_91") (pintype "bidirectional"))
      (node (ref "TP3") (pin "P$1") (pinfunction "1_P$1") (pintype "bidirectional"))
    )
    (net (code "137") (name "SPI1_NSS_SLAVE") (class "Default")
      (node (ref "SJ13") (pin "2") (pinfunction "2_2") (pintype "passive"))
      (node (ref "SJ14") (pin "2") (pinfunction "2_2") (pintype "passive"))
      (node (ref "STM32F303VET6") (pin "77") (pinfunction "PA15_77") (pintype "bidirectional"))
      (node (ref "TP21") (pin "P$1") (pinfunction "1_P$1") (pintype "bidirectional"))
    )
    (net (code "138") (name "SPI4_CLK_MASTER") (class "Default")
      (node (ref "JP8") (pin "1") (pinfunction "1_1") (pintype "passive"))
      (node (ref "RFM69HCW") (pin "13") (pinfunction "SCK_13") (pintype "input"))
      (node (ref "STM32F303VET6") (pin "1") (pinfunction "PE2_1") (pintype "bidirectional"))
      (node (ref "TP12") (pin "P$1") (pinfunction "1_P$1") (pintype "bidirectional"))
    )
    (net (code "139") (name "SPI4_CS_RFM69_MASTER") (class "Default")
      (node (ref "RFM69HCW") (pin "14") (pinfunction "~{SEL}_14") (pintype "input"))
      (node (ref "STM32F303VET6") (pin "3") (pinfunction "PE4_3") (pintype "bidirectional"))
      (node (ref "TP14") (pin "P$1") (pinfunction "1_P$1") (pintype "bidirectional"))
    )
    (net (code "140") (name "SPI4_CS_SDCARD_MASTER") (class "Default")
      (node (ref "JP2") (pin "1") (pinfunction "1_1") (pintype "passive"))
      (node (ref "STM32F303VET6") (pin "2") (pinfunction "PE3_2") (pintype "bidirectional"))
      (node (ref "TP13") (pin "P$1") (pinfunction "1_P$1") (pintype "bidirectional"))
    )
    (net (code "141") (name "SPI4_MISO_MASTER") (class "Default")
      (node (ref "JP7") (pin "1") (pinfunction "1_1") (pintype "passive"))
      (node (ref "RFM69HCW") (pin "1") (pinfunction "SDO_1") (pintype "output"))
      (node (ref "STM32F303VET6") (pin "4") (pinfunction "PE5_4") (pintype "bidirectional"))
      (node (ref "TP15") (pin "P$1") (pinfunction "1_P$1") (pintype "bidirectional"))
    )
    (net (code "142") (name "SPI4_MOSI_MASTER") (class "Default")
      (node (ref "JP3") (pin "1") (pinfunction "1_1") (pintype "passive"))
      (node (ref "RFM69HCW") (pin "12") (pinfunction "SDI_12") (pintype "input"))
      (node (ref "STM32F303VET6") (pin "5") (pinfunction "PE6_5") (pintype "bidirectional"))
      (node (ref "TP16") (pin "P$1") (pinfunction "1_P$1") (pintype "bidirectional"))
    )
    (net (code "143") (name "SWCLK") (class "Default")
      (node (ref "STM32F303VET6") (pin "76") (pinfunction "PA14_76") (pintype "bidirectional"))
      (node (ref "ST_LINK") (pin "1") (pinfunction "1_1") (pintype "passive"))
    )
    (net (code "144") (name "SWDIO") (class "Default")
      (node (ref "STM32F303VET6") (pin "72") (pinfunction "PA13_72") (pintype "bidirectional"))
      (node (ref "ST_LINK") (pin "2") (pinfunction "2_2") (pintype "passive"))
    )
    (net (code "145") (name "UART1_RX") (class "Default")
      (node (ref "PCB2") (pin "P$48") (pinfunction "GPIO14_P$48") (pintype "bidirectional"))
      (node (ref "STM32F303VET6") (pin "69") (pinfunction "PA10_69") (pintype "bidirectional"))
      (node (ref "UART1") (pin "1") (pinfunction "1_1") (pintype "passive"))
      (node (ref "UART_STM") (pin "4") (pinfunction "4_4") (pintype "passive"))
    )
    (net (code "146") (name "UART1_TX") (class "Default")
      (node (ref "PCB2") (pin "P$50") (pinfunction "GPIO15_P$50") (pintype "bidirectional"))
      (node (ref "STM32F303VET6") (pin "68") (pinfunction "PA9_68") (pintype "bidirectional"))
      (node (ref "UART1") (pin "2") (pinfunction "2_2") (pintype "passive"))
      (node (ref "UART_STM") (pin "5") (pinfunction "5_5") (pintype "passive"))
    )
    (net (code "147") (name "UART2_RX") (class "Default")
      (node (ref "STM32F303VET6") (pin "26") (pinfunction "PA3_26") (pintype "bidirectional"))
      (node (ref "SV1") (pin "4") (pinfunction "4_4") (pintype "passive"))
    )
    (net (code "148") (name "UART2_TX") (class "Default")
      (node (ref "STM32F303VET6") (pin "25") (pinfunction "PA2_25") (pintype "bidirectional"))
      (node (ref "SV1") (pin "5") (pinfunction "5_5") (pintype "passive"))
    )
    (net (code "149") (name "UART5_RX") (class "Default")
      (node (ref "SJ20") (pin "1") (pinfunction "1_1") (pintype "passive"))
      (node (ref "STM32F303VET6") (pin "83") (pinfunction "PD2_83") (pintype "bidirectional"))
    )
    (net (code "150") (name "UART5_TX") (class "Default")
      (node (ref "SJ21") (pin "1") (pinfunction "1_1") (pintype "passive"))
      (node (ref "STM32F303VET6") (pin "80") (pinfunction "PC12_80") (pintype "bidirectional"))
    )
    (net (code "151") (name "USART3_RX") (class "Default")
      (node (ref "R19") (pin "2") (pinfunction "2_2") (pintype "passive"))
      (node (ref "STM32F303VET6") (pin "95") (pinfunction "PB8_95") (pintype "bidirectional"))
    )
    (net (code "152") (name "USART3_TX") (class "Default")
      (node (ref "R18") (pin "2") (pinfunction "2_2") (pintype "passive"))
      (node (ref "STM32F303VET6") (pin "96") (pinfunction "PB9_96") (pintype "bidirectional"))
    )
    (net (code "153") (name "VBAT") (class "Default")
      (node (ref "G1") (pin "+") (pinfunction "+_+") (pintype "passive"))
      (node (ref "R8") (pin "2") (pinfunction "2_2") (pintype "passive"))
      (node (ref "STM32F303VET6") (pin "6") (pinfunction "VBAT_6") (pintype "bidirectional"))
    )
    (net (code "154") (name "VMOS1") (class "Default")
      (node (ref "Q21") (pin "1") (pinfunction "G_1") (pintype "bidirectional"))
      (node (ref "STM32F303VET6") (pin "15") (pinfunction "PC0_15") (pintype "bidirectional"))
      (node (ref "TP6") (pin "1") (pinfunction "1_1") (pintype "bidirectional"))
    )
    (net (code "155") (name "VMOS2") (class "Default")
      (node (ref "Q22") (pin "1") (pinfunction "G_1") (pintype "bidirectional"))
      (node (ref "STM32F303VET6") (pin "16") (pinfunction "PC1_16") (pintype "bidirectional"))
    )
    (net (code "156") (name "VMOS3") (class "Default")
      (node (ref "Q33") (pin "1") (pinfunction "G_1") (pintype "bidirectional"))
      (node (ref "STM32F303VET6") (pin "17") (pinfunction "PC2_17") (pintype "bidirectional"))
    )
    (net (code "157") (name "VREF+") (class "Default")
      (node (ref "C23") (pin "1") (pinfunction "1_1") (pintype "passive"))
      (node (ref "JP1") (pin "3") (pinfunction "3_3") (pintype "passive"))
      (node (ref "PS1") (pin "6") (pinfunction "VOUT_6") (pintype "input"))
      (node (ref "SJ2") (pin "1") (pinfunction "1_1") (pintype "passive"))
      (node (ref "STM32F303VET6") (pin "21") (pinfunction "VREF+_21") (pintype "bidirectional"))
      (node (ref "TP7") (pin "1") (pinfunction "1_1") (pintype "bidirectional"))
    )
    (net (code "158") (name "VSIG1") (class "Default")
      (node (ref "CV1") (pin "1") (pinfunction "1_1") (pintype "passive"))
      (node (ref "D2") (pin "K") (pinfunction "C_K") (pintype "passive"))
      (node (ref "D30") (pin "A") (pinfunction "A_A") (pintype "passive"))
      (node (ref "R25") (pin "2") (pinfunction "2_2") (pintype "passive"))
      (node (ref "STM32F303VET6") (pin "23") (pinfunction "PA0_23") (pintype "bidirectional"))
      (node (ref "TP20") (pin "1") (pinfunction "1_1") (pintype "bidirectional"))
    )
    (net (code "159") (name "VSIG2") (class "Default")
      (node (ref "CV2") (pin "1") (pinfunction "1_1") (pintype "passive"))
      (node (ref "D3") (pin "K") (pinfunction "C_K") (pintype "passive"))
      (node (ref "D31") (pin "A") (pinfunction "A_A") (pintype "passive"))
      (node (ref "R26") (pin "2") (pinfunction "2_2") (pintype "passive"))
      (node (ref "STM32F303VET6") (pin "24") (pinfunction "PA1_24") (pintype "bidirectional"))
    )
    (net (code "160") (name "VSIG3") (class "Default")
      (node (ref "CV3") (pin "1") (pinfunction "1_1") (pintype "passive"))
      (node (ref "D32") (pin "A") (pinfunction "A_A") (pintype "passive"))
      (node (ref "D4") (pin "K") (pinfunction "C_K") (pintype "passive"))
      (node (ref "R27") (pin "2") (pinfunction "2_2") (pintype "passive"))
      (node (ref "STM32F303VET6") (pin "19") (pinfunction "PF2_19") (pintype "bidirectional"))
    )
    (net (code "161") (name "unconnected-(CT1-3-PadP$3)") (class "Default")
      (node (ref "CT1") (pin "P$3") (pinfunction "3_P$3") (pintype "bidirectional"))
    )
    (net (code "162") (name "unconnected-(CT2-3-PadP$3)") (class "Default")
      (node (ref "CT2") (pin "P$3") (pinfunction "3_P$3") (pintype "bidirectional"))
    )
    (net (code "163") (name "unconnected-(CT3-3-PadP$3)") (class "Default")
      (node (ref "CT3") (pin "P$3") (pinfunction "3_P$3") (pintype "bidirectional"))
    )
    (net (code "164") (name "unconnected-(CT4-3-PadP$3)") (class "Default")
      (node (ref "CT4") (pin "P$3") (pinfunction "3_P$3") (pintype "bidirectional"))
    )
    (net (code "165") (name "unconnected-(CT5-3-PadP$3)") (class "Default")
      (node (ref "CT5") (pin "P$3") (pinfunction "3_P$3") (pintype "bidirectional"))
    )
    (net (code "166") (name "unconnected-(CT6-3-PadP$3)") (class "Default")
      (node (ref "CT6") (pin "P$3") (pinfunction "3_P$3") (pintype "bidirectional"))
    )
    (net (code "167") (name "unconnected-(CT7-3-PadP$3)") (class "Default")
      (node (ref "CT7") (pin "P$3") (pinfunction "3_P$3") (pintype "bidirectional"))
    )
    (net (code "168") (name "unconnected-(CT8-3-PadP$3)") (class "Default")
      (node (ref "CT8") (pin "P$3") (pinfunction "3_P$3") (pintype "bidirectional"))
    )
    (net (code "169") (name "unconnected-(CT9-3-PadP$3)") (class "Default")
      (node (ref "CT9") (pin "P$3") (pinfunction "3_P$3") (pintype "bidirectional"))
    )
    (net (code "170") (name "unconnected-(EXPANSION-Pad11)") (class "Default")
      (node (ref "EXPANSION") (pin "11") (pinfunction "11_11") (pintype "passive"))
    )
    (net (code "171") (name "unconnected-(EXPANSION-Pad12)") (class "Default")
      (node (ref "EXPANSION") (pin "12") (pinfunction "12_12") (pintype "passive"))
    )
    (net (code "172") (name "unconnected-(EXPANSION-Pad13)") (class "Default")
      (node (ref "EXPANSION") (pin "13") (pinfunction "13_13") (pintype "passive"))
    )
    (net (code "173") (name "unconnected-(PCB2-3V3-PadP$41)") (class "Default")
      (node (ref "PCB2") (pin "P$41") (pinfunction "3V3_P$41") (pintype "bidirectional"))
    )
    (net (code "174") (name "unconnected-(PCB2-GPIO5-PadP$69)") (class "Default")
      (node (ref "PCB2") (pin "P$69") (pinfunction "GPIO5_P$69") (pintype "bidirectional"))
    )
    (net (code "175") (name "unconnected-(PCB2-GPIO6-PadP$71)") (class "Default")
      (node (ref "PCB2") (pin "P$71") (pinfunction "GPIO6_P$71") (pintype "bidirectional"))
    )
    (net (code "176") (name "unconnected-(PCB2-GPIO7-PadP$66)") (class "Default")
      (node (ref "PCB2") (pin "P$66") (pinfunction "GPIO7_P$66") (pintype "bidirectional"))
    )
    (net (code "177") (name "unconnected-(PCB2-GPIO12-PadP$72)") (class "Default")
      (node (ref "PCB2") (pin "P$72") (pinfunction "GPIO12_P$72") (pintype "bidirectional"))
    )
    (net (code "178") (name "unconnected-(PCB2-GPIO13-PadP$73)") (class "Default")
      (node (ref "PCB2") (pin "P$73") (pinfunction "GPIO13_P$73") (pintype "bidirectional"))
    )
    (net (code "179") (name "unconnected-(PCB2-GPIO18-PadP$52)") (class "Default")
      (node (ref "PCB2") (pin "P$52") (pinfunction "GPIO18_P$52") (pintype "bidirectional"))
    )
    (net (code "180") (name "unconnected-(PCB2-GPIO19-PadP$75)") (class "Default")
      (node (ref "PCB2") (pin "P$75") (pinfunction "GPIO19_P$75") (pintype "bidirectional"))
    )
    (net (code "181") (name "unconnected-(PCB2-GPIO21-PadP$80)") (class "Default")
      (node (ref "PCB2") (pin "P$80") (pinfunction "GPIO21_P$80") (pintype "bidirectional"))
    )
    (net (code "182") (name "unconnected-(PCB2-GPIO22-PadP$55)") (class "Default")
      (node (ref "PCB2") (pin "P$55") (pinfunction "GPIO22_P$55") (pintype "bidirectional"))
    )
    (net (code "183") (name "unconnected-(PCB2-GPIO23-PadP$56)") (class "Default")
      (node (ref "PCB2") (pin "P$56") (pinfunction "GPIO23_P$56") (pintype "bidirectional"))
    )
    (net (code "184") (name "unconnected-(PCB2-GPIO24-PadP$58)") (class "Default")
      (node (ref "PCB2") (pin "P$58") (pinfunction "GPIO24_P$58") (pintype "bidirectional"))
    )
    (net (code "185") (name "unconnected-(PCB2-GPIO25-PadP$62)") (class "Default")
      (node (ref "PCB2") (pin "P$62") (pinfunction "GPIO25_P$62") (pintype "bidirectional"))
    )
    (net (code "186") (name "unconnected-(PCB2-GPIO26-PadP$77)") (class "Default")
      (node (ref "PCB2") (pin "P$77") (pinfunction "GPIO26_P$77") (pintype "bidirectional"))
    )
    (net (code "187") (name "unconnected-(PCB2-ID_SC*-PadP$68)") (class "Default")
      (node (ref "PCB2") (pin "P$68") (pinfunction "ID_SC*_P$68") (pintype "bidirectional"))
    )
    (net (code "188") (name "unconnected-(PCB2-ID_SD*-PadP$67)") (class "Default")
      (node (ref "PCB2") (pin "P$67") (pinfunction "ID_SD*_P$67") (pintype "bidirectional"))
    )
    (net (code "189") (name "unconnected-(PS1-DNC_1-Pad1)") (class "Default")
      (node (ref "PS1") (pin "1") (pinfunction "DNC_1_1") (pintype "bidirectional"))
    )
    (net (code "190") (name "unconnected-(PS1-DNC_2-Pad5)") (class "Default")
      (node (ref "PS1") (pin "5") (pinfunction "DNC_2_5") (pintype "bidirectional"))
    )
    (net (code "191") (name "unconnected-(PS1-DNC_3-Pad7)") (class "Default")
      (node (ref "PS1") (pin "7") (pinfunction "DNC_3_7") (pintype "bidirectional"))
    )
    (net (code "192") (name "unconnected-(PS1-DNC_4-Pad8)") (class "Default")
      (node (ref "PS1") (pin "8") (pinfunction "DNC_4_8") (pintype "bidirectional"))
    )
    (net (code "193") (name "unconnected-(PS1-~{SHDN}-Pad3)") (class "Default")
      (node (ref "PS1") (pin "3") (pinfunction "~{SHDN}_3") (pintype "input"))
    )
    (net (code "194") (name "unconnected-(RFM69HCW-CLK-Pad5)") (class "Default")
      (node (ref "RFM69HCW") (pin "5") (pinfunction "CLK_5") (pintype "output"))
    )
    (net (code "195") (name "unconnected-(RFM69HCW-DCLK{slash}CFIL{slash}FFIT-Pad4)") (class "Default")
      (node (ref "RFM69HCW") (pin "4") (pinfunction "DCLK/CFIL/FFIT_4") (pintype "bidirectional"))
    )
    (net (code "196") (name "unconnected-(RFM69HCW-FSK{slash}DATA{slash}NFFS-Pad3)") (class "Default")
      (node (ref "RFM69HCW") (pin "3") (pinfunction "FSK/DATA/NFFS_3") (pintype "bidirectional"))
    )
    (net (code "197") (name "unconnected-(RFM69HCW-~{INT}-Pad11)") (class "Default")
      (node (ref "RFM69HCW") (pin "11") (pinfunction "~{INT}_11") (pintype "bidirectional"))
    )
    (net (code "198") (name "unconnected-(STM32F303VET6-PA8-Pad67)") (class "Default")
      (node (ref "STM32F303VET6") (pin "67") (pinfunction "PA8_67") (pintype "bidirectional"))
    )
    (net (code "199") (name "unconnected-(STM32F303VET6-PA11-Pad70)") (class "Default")
      (node (ref "STM32F303VET6") (pin "70") (pinfunction "PA11_70") (pintype "bidirectional"))
    )
    (net (code "200") (name "unconnected-(STM32F303VET6-PB0-Pad35)") (class "Default")
      (node (ref "STM32F303VET6") (pin "35") (pinfunction "PB0_35") (pintype "bidirectional"))
    )
    (net (code "201") (name "unconnected-(STM32F303VET6-PB1-Pad36)") (class "Default")
      (node (ref "STM32F303VET6") (pin "36") (pinfunction "PB1_36") (pintype "bidirectional"))
    )
    (net (code "202") (name "unconnected-(STM32F303VET6-PB6-Pad92)") (class "Default")
      (node (ref "STM32F303VET6") (pin "92") (pinfunction "PB6_92") (pintype "bidirectional"))
    )
    (net (code "203") (name "unconnected-(STM32F303VET6-PB7-Pad93)") (class "Default")
      (node (ref "STM32F303VET6") (pin "93") (pinfunction "PB7_93") (pintype "bidirectional"))
    )
    (net (code "204") (name "unconnected-(STM32F303VET6-PB10-Pad47)") (class "Default")
      (node (ref "STM32F303VET6") (pin "47") (pinfunction "PB10_47") (pintype "bidirectional"))
    )
    (net (code "205") (name "unconnected-(STM32F303VET6-PB13-Pad52)") (class "Default")
      (node (ref "STM32F303VET6") (pin "52") (pinfunction "PB13_52") (pintype "bidirectional"))
    )
    (net (code "206") (name "unconnected-(STM32F303VET6-PC13-Pad7)") (class "Default")
      (node (ref "STM32F303VET6") (pin "7") (pinfunction "PC13_7") (pintype "bidirectional"))
    )
    (net (code "207") (name "unconnected-(STM32F303VET6-PD0-Pad81)") (class "Default")
      (node (ref "STM32F303VET6") (pin "81") (pinfunction "PD0_81") (pintype "bidirectional"))
    )
    (net (code "208") (name "unconnected-(STM32F303VET6-PD1-Pad82)") (class "Default")
      (node (ref "STM32F303VET6") (pin "82") (pinfunction "PD1_82") (pintype "bidirectional"))
    )
    (net (code "209") (name "unconnected-(STM32F303VET6-PD3-Pad84)") (class "Default")
      (node (ref "STM32F303VET6") (pin "84") (pinfunction "PD3_84") (pintype "bidirectional"))
    )
    (net (code "210") (name "unconnected-(STM32F303VET6-PD4-Pad85)") (class "Default")
      (node (ref "STM32F303VET6") (pin "85") (pinfunction "PD4_85") (pintype "bidirectional"))
    )
    (net (code "211") (name "unconnected-(STM32F303VET6-PD5-Pad86)") (class "Default")
      (node (ref "STM32F303VET6") (pin "86") (pinfunction "PD5_86") (pintype "bidirectional"))
    )
    (net (code "212") (name "unconnected-(STM32F303VET6-PD7-Pad88)") (class "Default")
      (node (ref "STM32F303VET6") (pin "88") (pinfunction "PD7_88") (pintype "bidirectional"))
    )
    (net (code "213") (name "unconnected-(STM32F303VET6-PF4-Pad27)") (class "Default")
      (node (ref "STM32F303VET6") (pin "27") (pinfunction "PF4_27") (pintype "bidirectional"))
    )
    (net (code "214") (name "unconnected-(STM32F303VET6-PF9-Pad10)") (class "Default")
      (node (ref "STM32F303VET6") (pin "10") (pinfunction "PF9_10") (pintype "bidirectional"))
    )
    (net (code "215") (name "unconnected-(STM32F303VET6-PF10-Pad11)") (class "Default")
      (node (ref "STM32F303VET6") (pin "11") (pinfunction "PF10_11") (pintype "bidirectional"))
    )
    (net (code "216") (name "unconnected-(SV2-Pad2)") (class "Default")
      (node (ref "SV2") (pin "2") (pinfunction "2_2") (pintype "passive"))
    )
    (net (code "217") (name "unconnected-(U$7-DAT1-PadPIN8)") (class "Default")
      (node (ref "U$7") (pin "PIN8") (pinfunction "DAT1_PIN8") (pintype "bidirectional"))
    )
    (net (code "218") (name "unconnected-(U$7-DAT2-PadPIN1)") (class "Default")
      (node (ref "U$7") (pin "PIN1") (pinfunction "DAT2_PIN1") (pintype "bidirectional"))
    )
    (net (code "219") (name "unconnected-(U1-IO2-Pad24)") (class "Default")
      (node (ref "U1") (pin "24") (pinfunction "IO2_24") (pintype "bidirectional"))
    )
    (net (code "220") (name "unconnected-(U1-IO4-Pad26)") (class "Default")
      (node (ref "U1") (pin "26") (pinfunction "IO4_26") (pintype "bidirectional"))
    )
    (net (code "221") (name "unconnected-(U1-IO5-Pad29)") (class "Default")
      (node (ref "U1") (pin "29") (pinfunction "IO5_29") (pintype "bidirectional"))
    )
    (net (code "222") (name "unconnected-(U1-IO16-Pad27)") (class "Default")
      (node (ref "U1") (pin "27") (pinfunction "IO16_27") (pintype "bidirectional"))
    )
    (net (code "223") (name "unconnected-(U1-IO17-Pad28)") (class "Default")
      (node (ref "U1") (pin "28") (pinfunction "IO17_28") (pintype "bidirectional"))
    )
    (net (code "224") (name "unconnected-(U1-IO23-Pad37)") (class "Default")
      (node (ref "U1") (pin "37") (pinfunction "IO23_37") (pintype "bidirectional"))
    )
    (net (code "225") (name "unconnected-(U1-IO25-Pad10)") (class "Default")
      (node (ref "U1") (pin "10") (pinfunction "IO25_10") (pintype "bidirectional"))
    )
    (net (code "226") (name "unconnected-(U1-IO26-Pad11)") (class "Default")
      (node (ref "U1") (pin "11") (pinfunction "IO26_11") (pintype "bidirectional"))
    )
    (net (code "227") (name "unconnected-(U1-IO27-Pad12)") (class "Default")
      (node (ref "U1") (pin "12") (pinfunction "IO27_12") (pintype "bidirectional"))
    )
    (net (code "228") (name "unconnected-(U1-IO32-Pad8)") (class "Default")
      (node (ref "U1") (pin "8") (pinfunction "IO32_8") (pintype "bidirectional"))
    )
    (net (code "229") (name "unconnected-(U1-IO33-Pad9)") (class "Default")
      (node (ref "U1") (pin "9") (pinfunction "IO33_9") (pintype "bidirectional"))
    )
    (net (code "230") (name "unconnected-(U1-IO34-Pad6)") (class "Default")
      (node (ref "U1") (pin "6") (pinfunction "IO34_6") (pintype "bidirectional"))
    )
    (net (code "231") (name "unconnected-(U1-IO35-Pad7)") (class "Default")
      (node (ref "U1") (pin "7") (pinfunction "IO35_7") (pintype "bidirectional"))
    )
    (net (code "232") (name "unconnected-(U1-SCL{slash}CLK-Pad20)") (class "Default")
      (node (ref "U1") (pin "20") (pinfunction "SCL/CLK_20") (pintype "bidirectional"))
    )
    (net (code "233") (name "unconnected-(U1-SCS{slash}CMD-Pad19)") (class "Default")
      (node (ref "U1") (pin "19") (pinfunction "SCS/CMD_19") (pintype "bidirectional"))
    )
    (net (code "234") (name "unconnected-(U1-SDI{slash}SD1-Pad22)") (class "Default")
      (node (ref "U1") (pin "22") (pinfunction "SDI/SD1_22") (pintype "bidirectional"))
    )
    (net (code "235") (name "unconnected-(U1-SDO{slash}SD0-Pad21)") (class "Default")
      (node (ref "U1") (pin "21") (pinfunction "SDO/SD0_21") (pintype "bidirectional"))
    )
    (net (code "236") (name "unconnected-(U1-SENSOR_VN-Pad5)") (class "Default")
      (node (ref "U1") (pin "5") (pinfunction "SENSOR_VN_5") (pintype "input"))
    )
    (net (code "237") (name "unconnected-(U1-SENSOR_VP-Pad4)") (class "Default")
      (node (ref "U1") (pin "4") (pinfunction "SENSOR_VP_4") (pintype "input"))
    )
    (net (code "238") (name "unconnected-(U1-SHD{slash}SD2-Pad17)") (class "Default")
      (node (ref "U1") (pin "17") (pinfunction "SHD/SD2_17") (pintype "bidirectional"))
    )
    (net (code "239") (name "unconnected-(U1-SWP{slash}SD3-Pad18)") (class "Default")
      (node (ref "U1") (pin "18") (pinfunction "SWP/SD3_18") (pintype "bidirectional"))
    )
    (net (code "240") (name "unconnected-(USB-C-D1+-PadA6)") (class "Default")
      (node (ref "USB-C") (pin "A6") (pinfunction "D1+_A6") (pintype "passive"))
    )
    (net (code "241") (name "unconnected-(USB-C-D1--PadA7)") (class "Default")
      (node (ref "USB-C") (pin "A7") (pinfunction "D1-_A7") (pintype "passive"))
    )
  )
)
